# miniPET_final.net
KiCad netlist of a schematic drawn in EAGLE
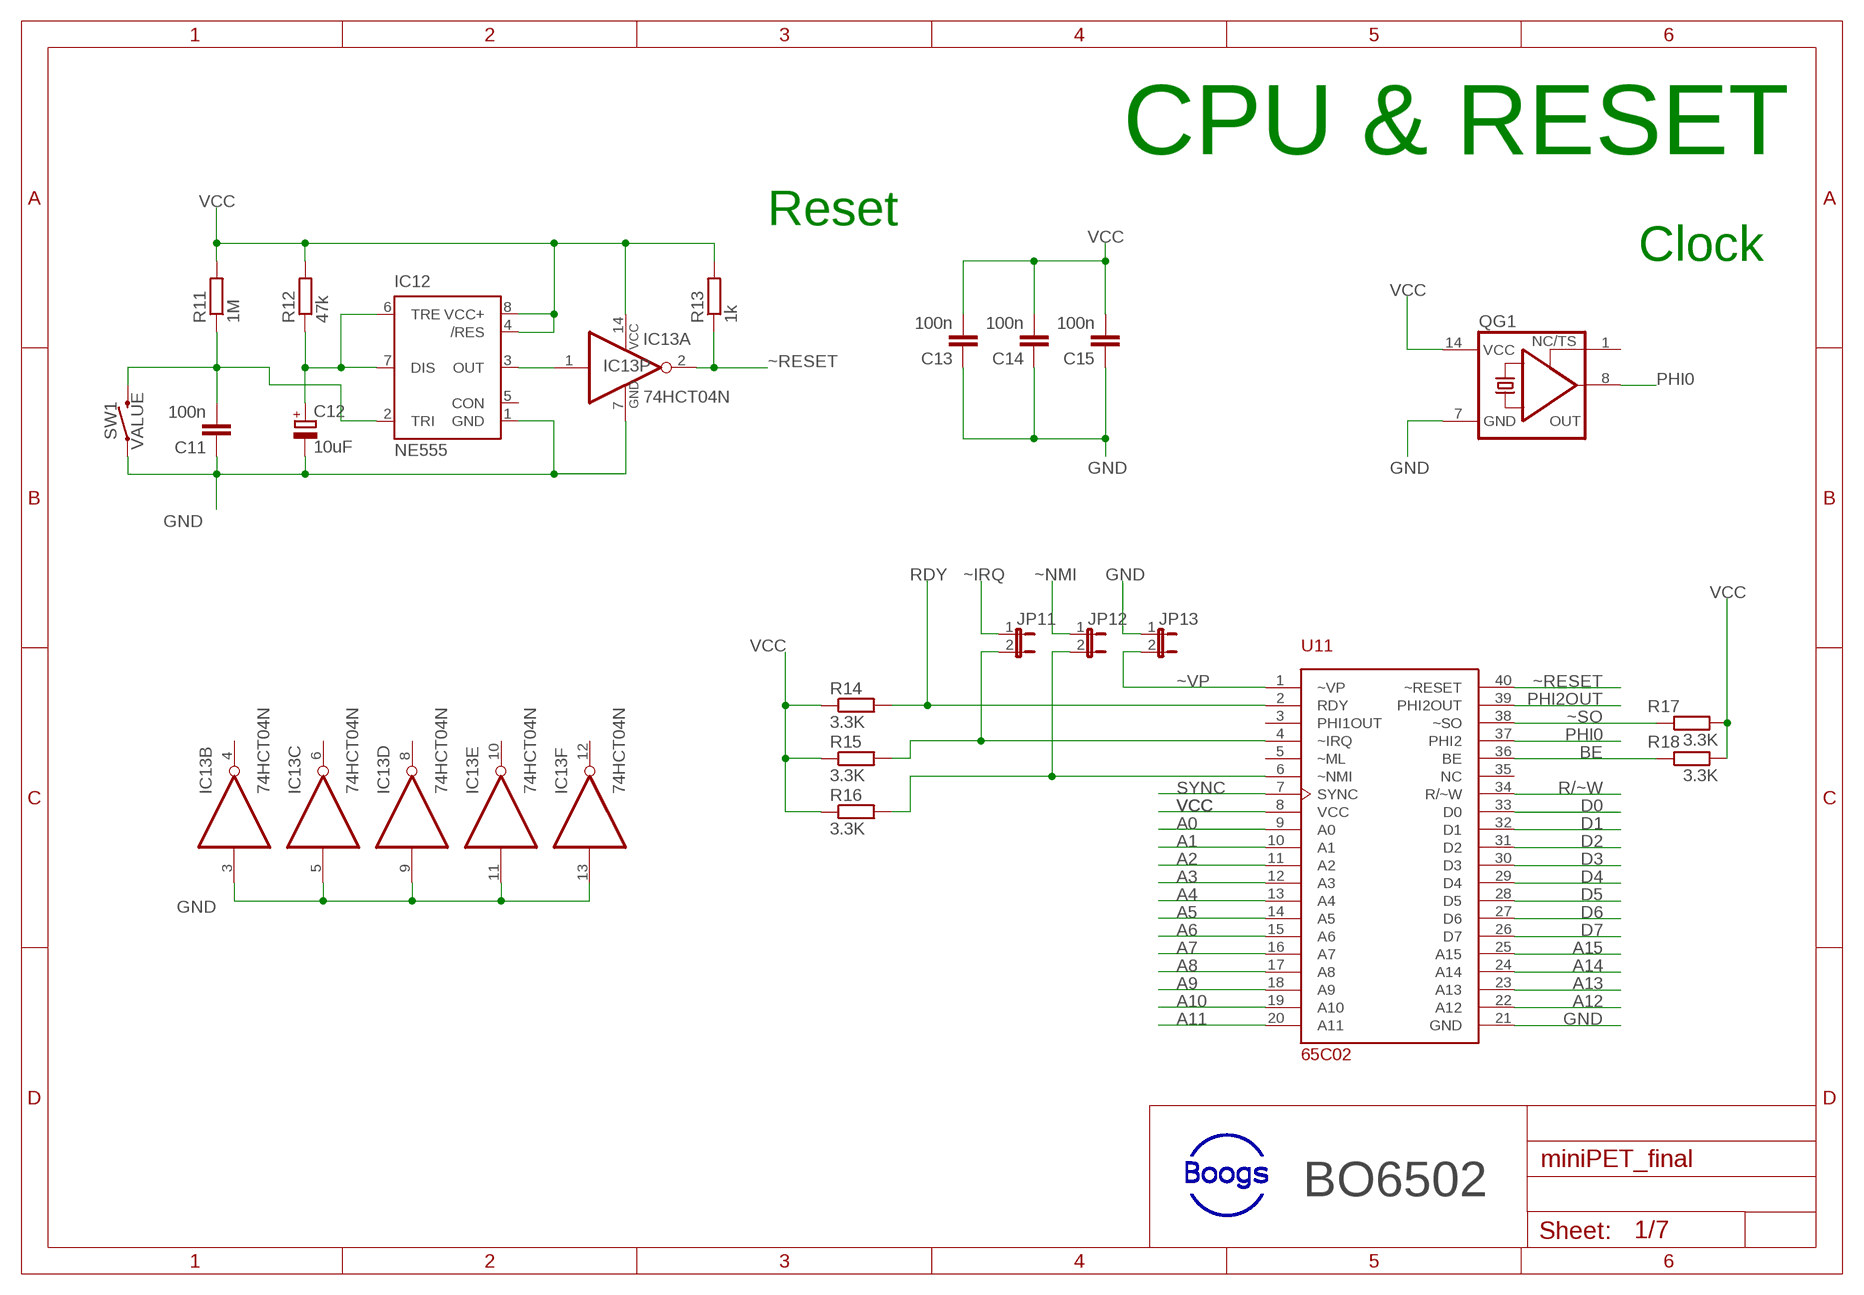
[diagram p0: schematic, sheet 1]
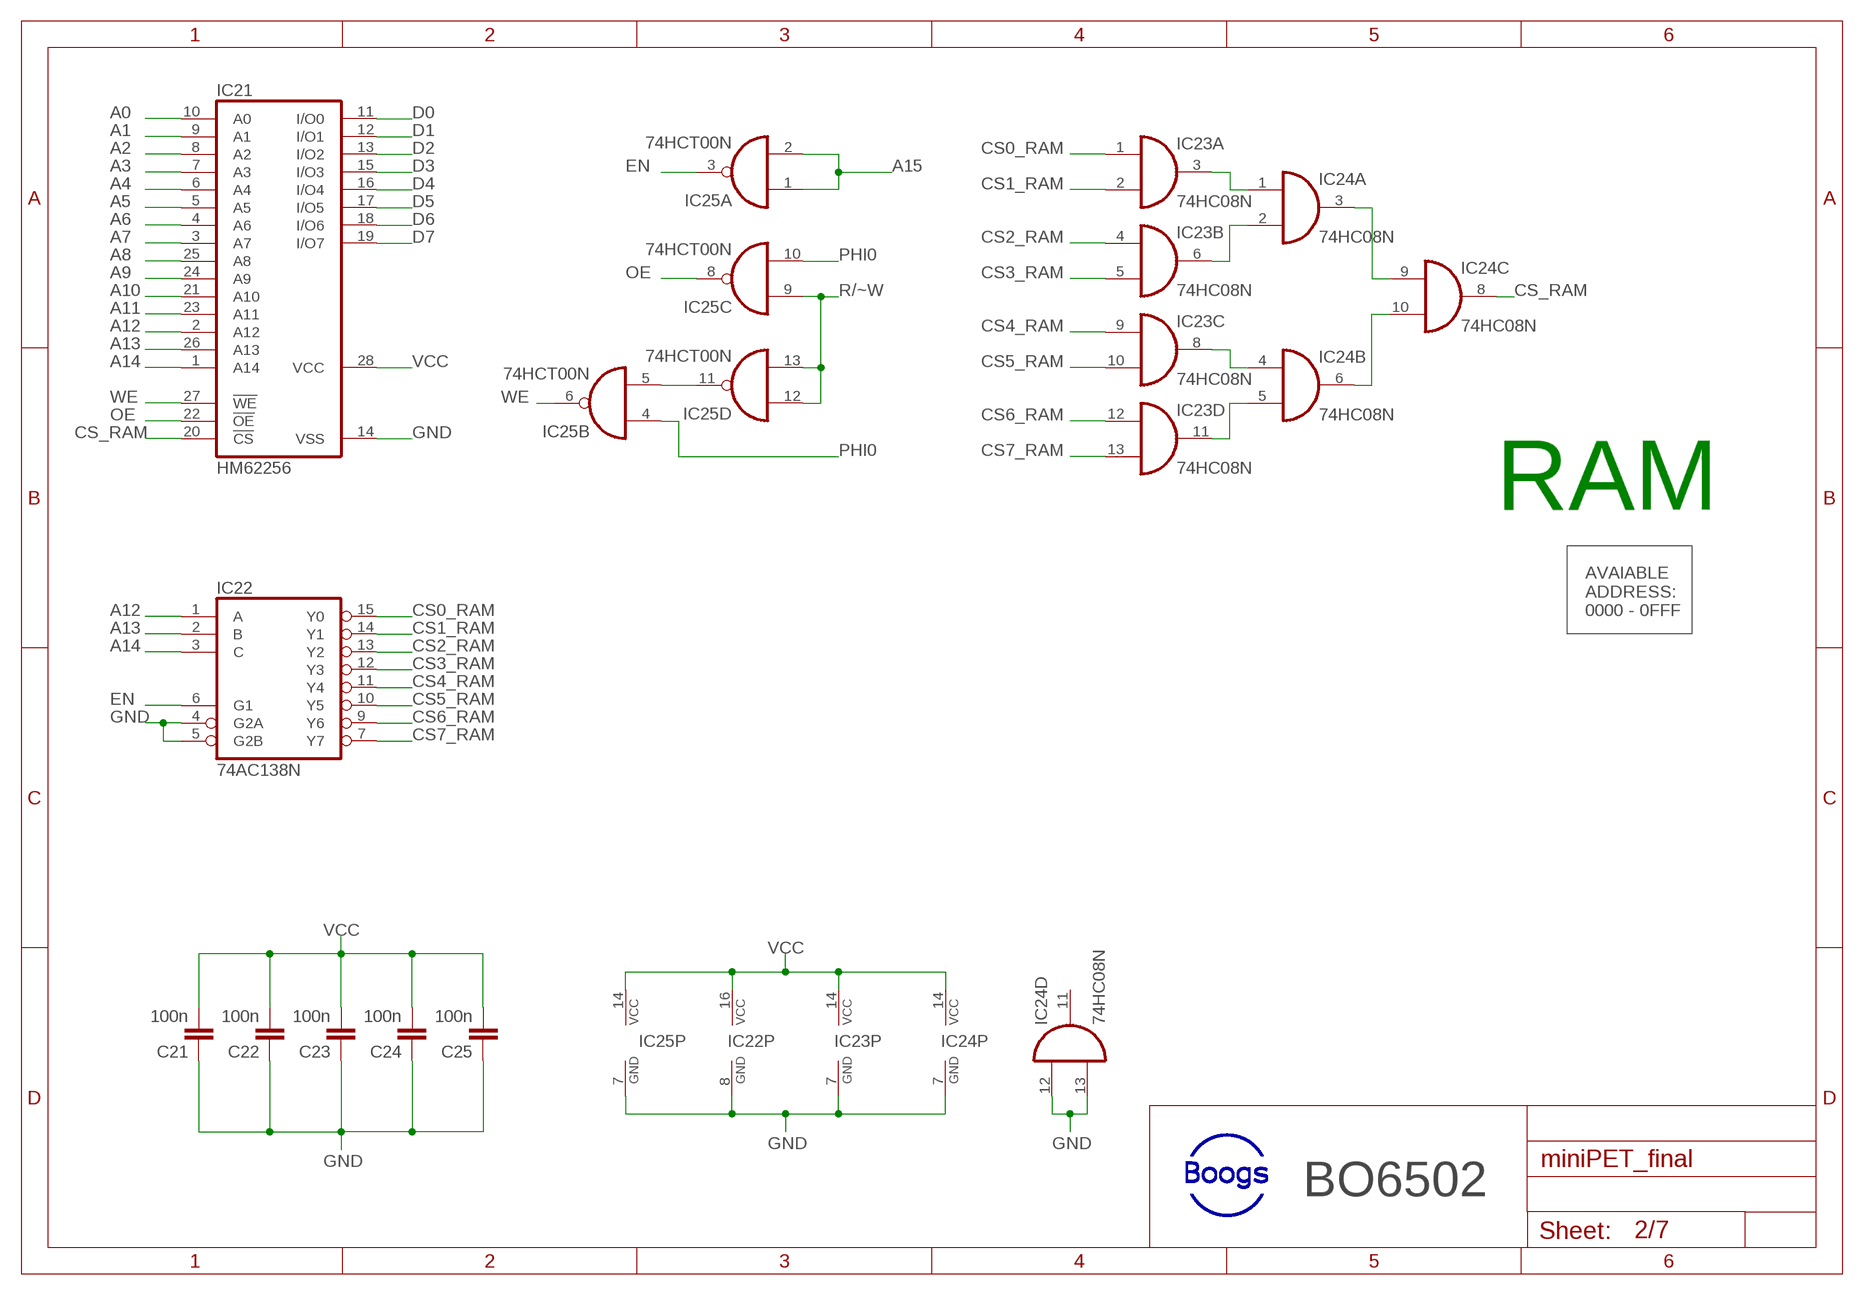
[diagram p1: schematic, sheet 2]
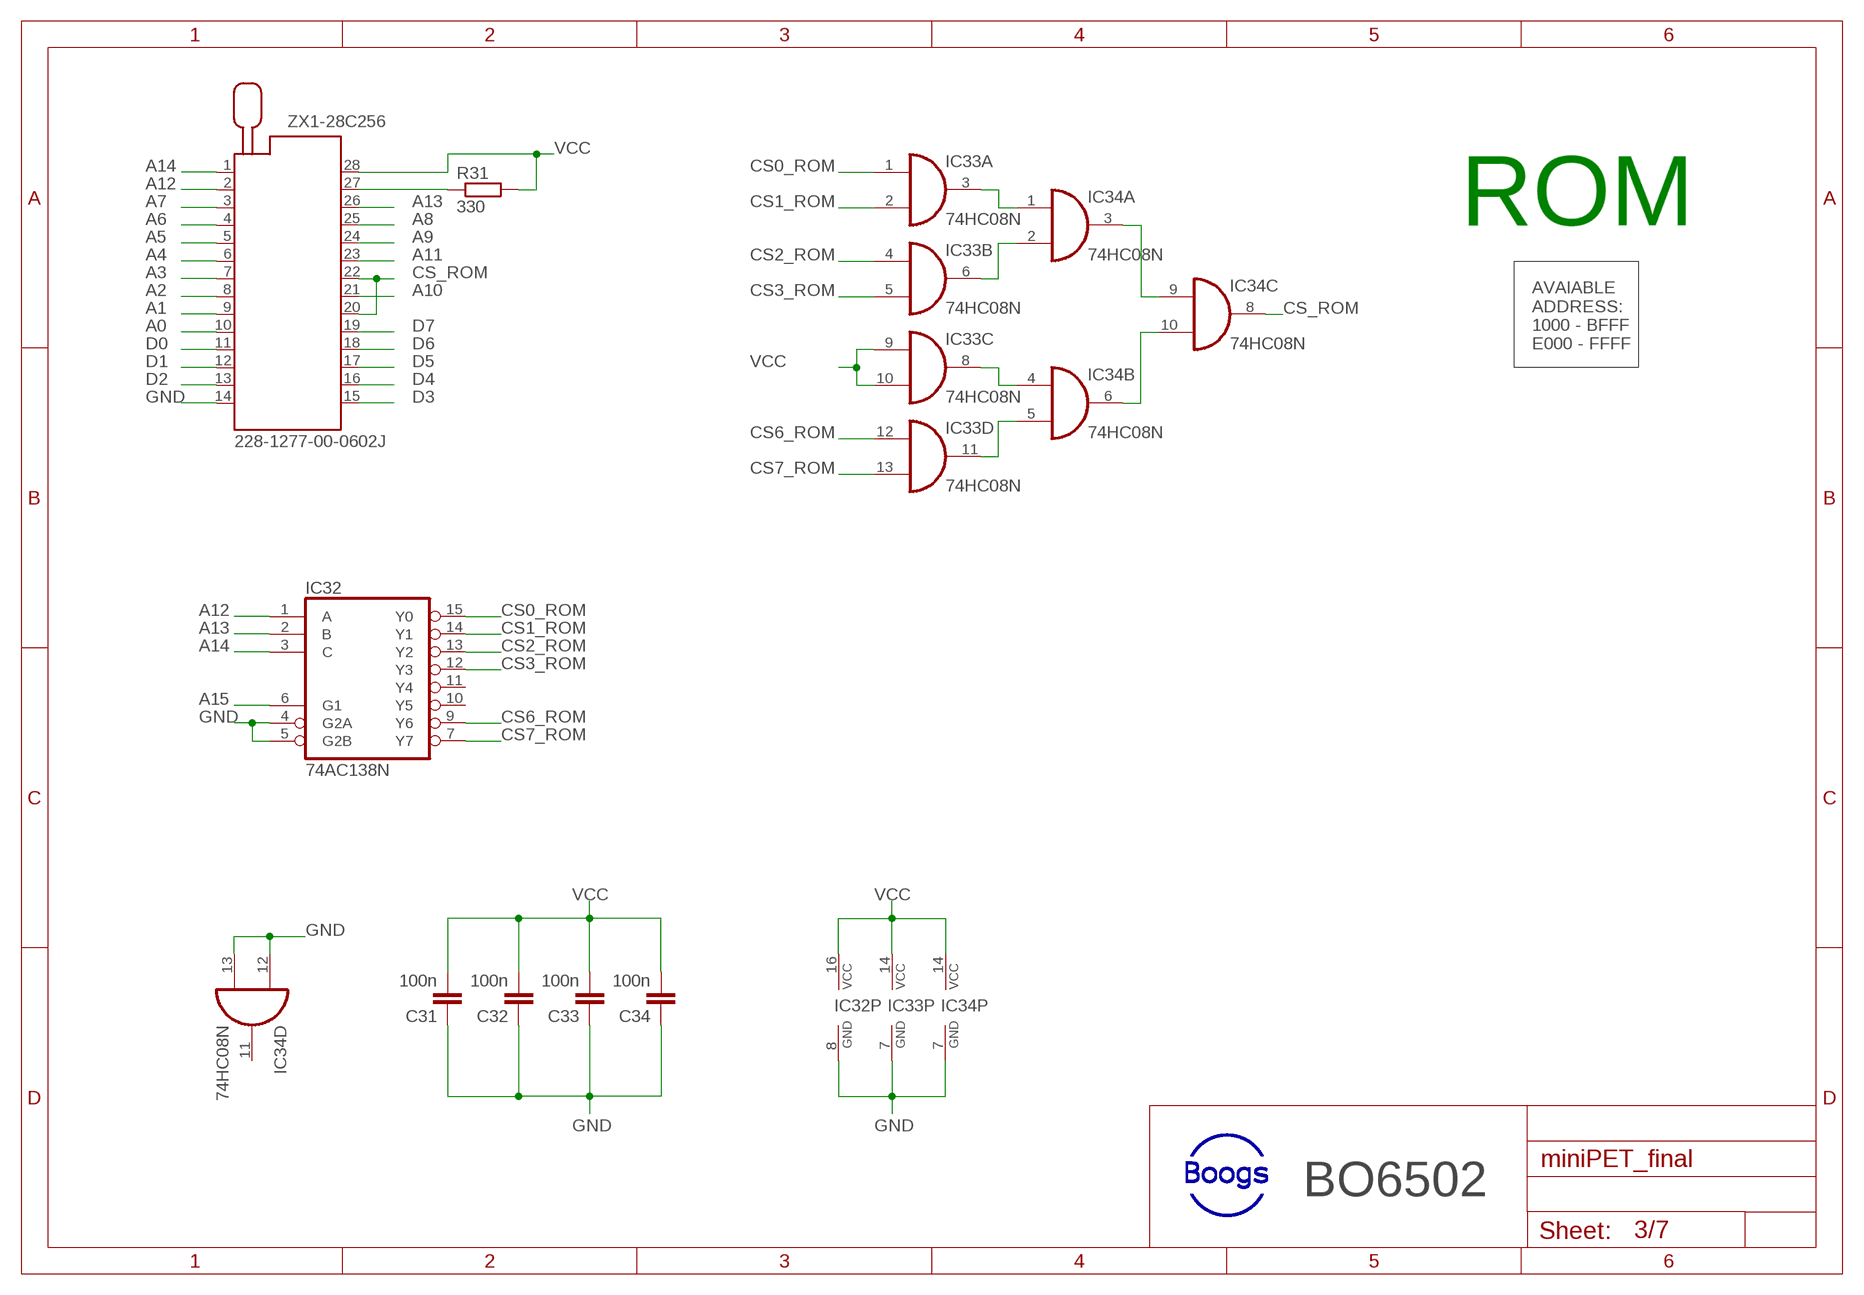
[diagram p2: schematic, sheet 3]
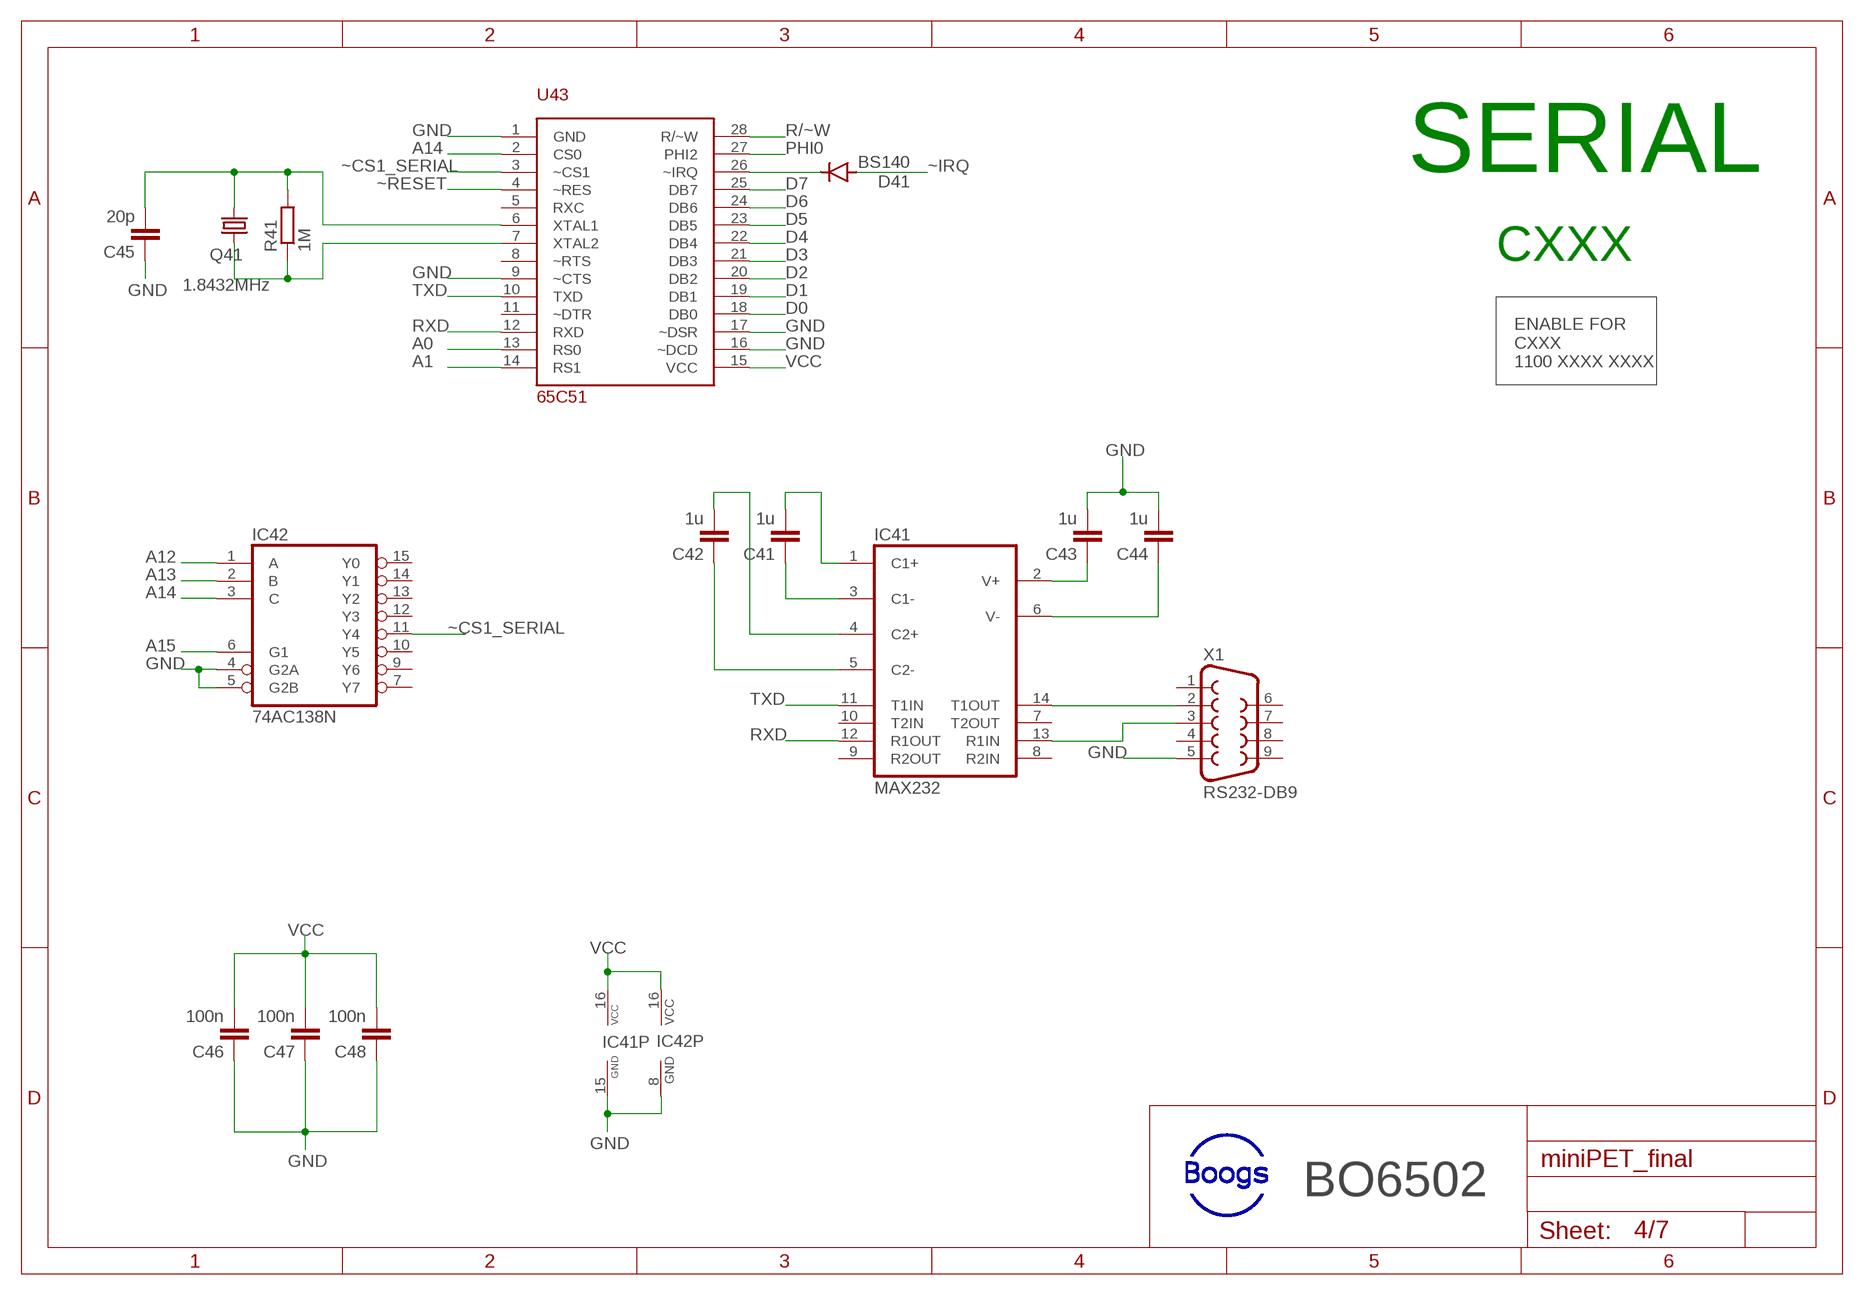
[diagram p3: schematic, sheet 4]
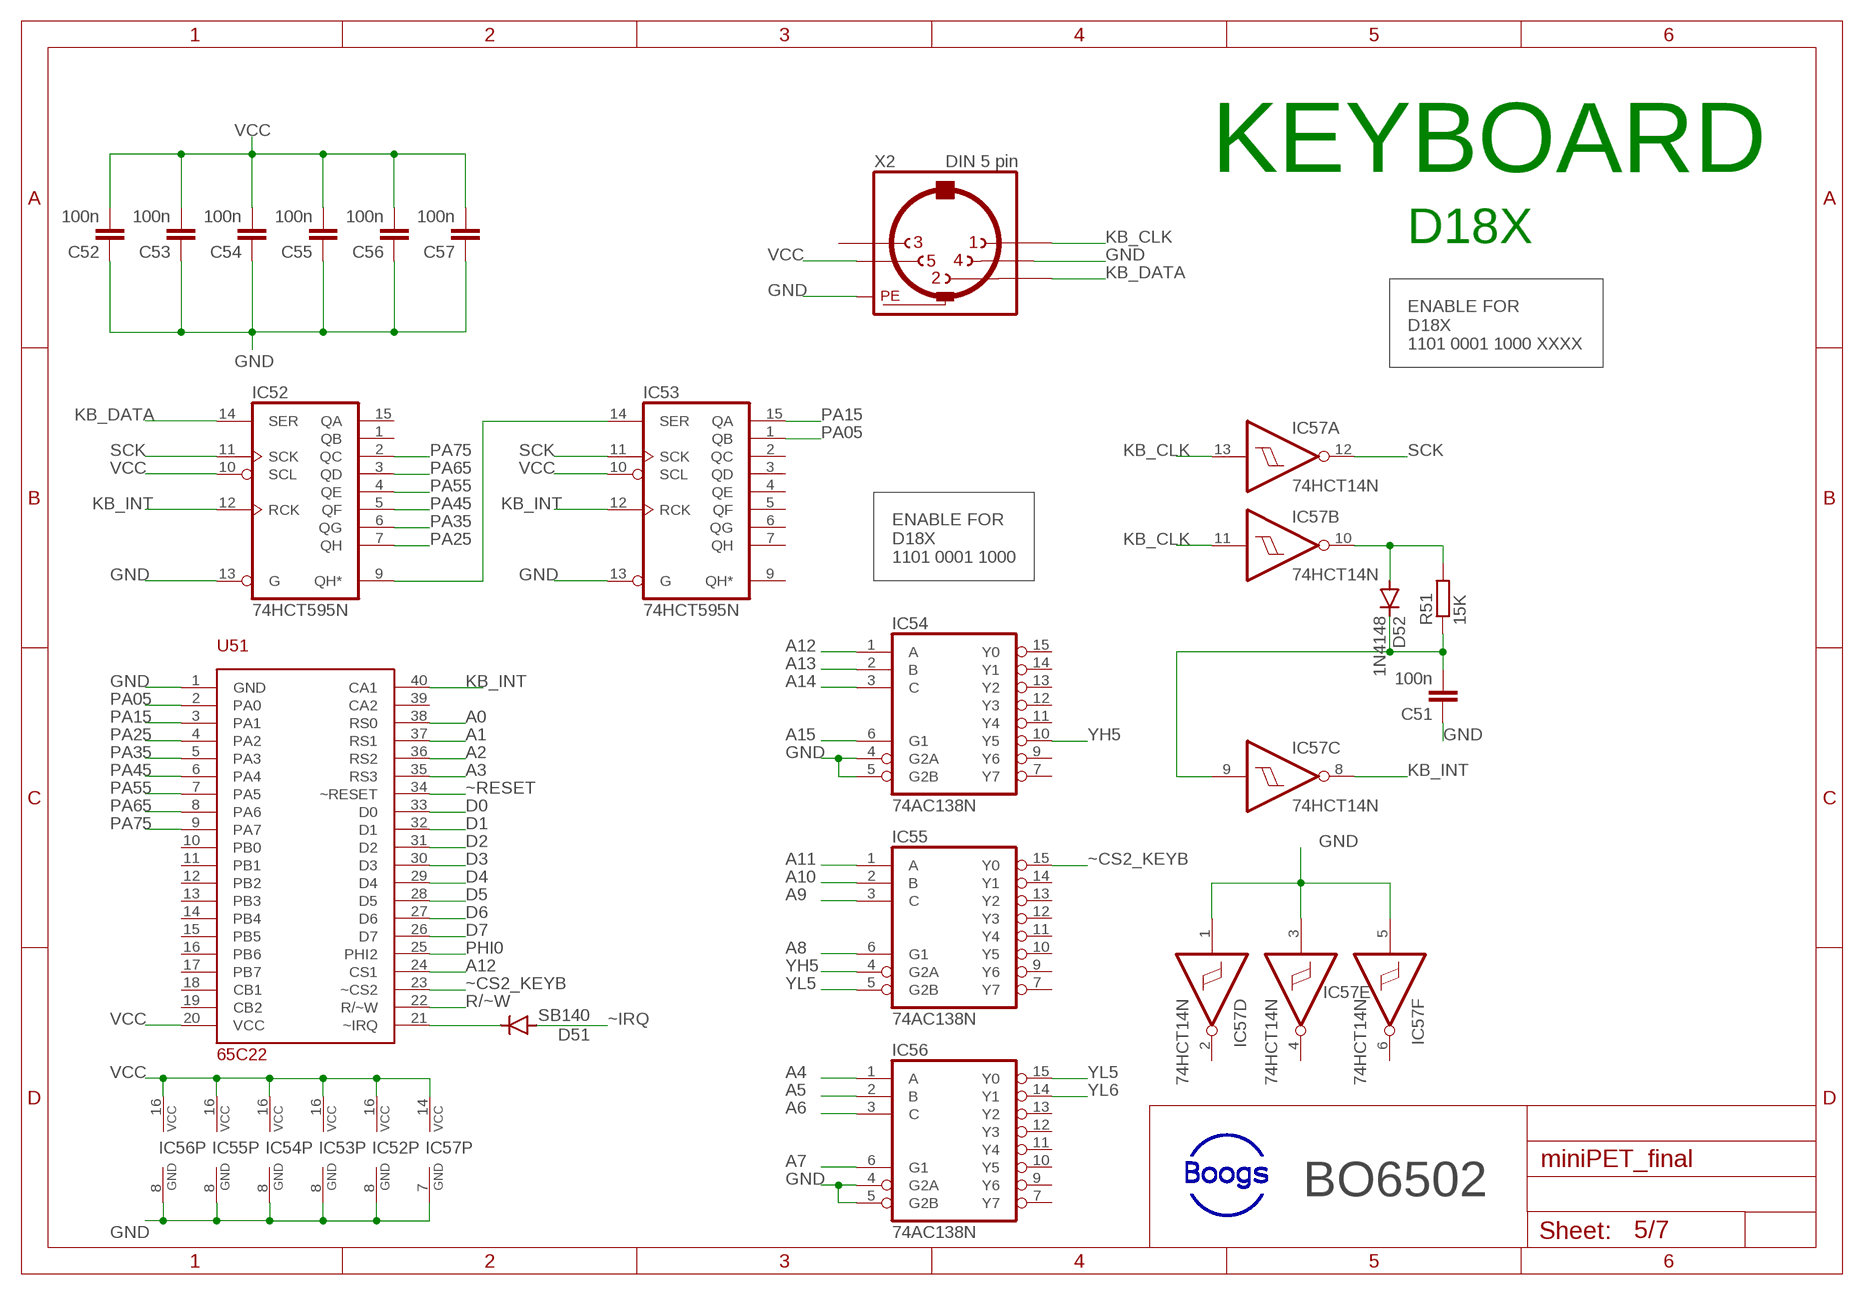
[diagram p4: schematic, sheet 5]
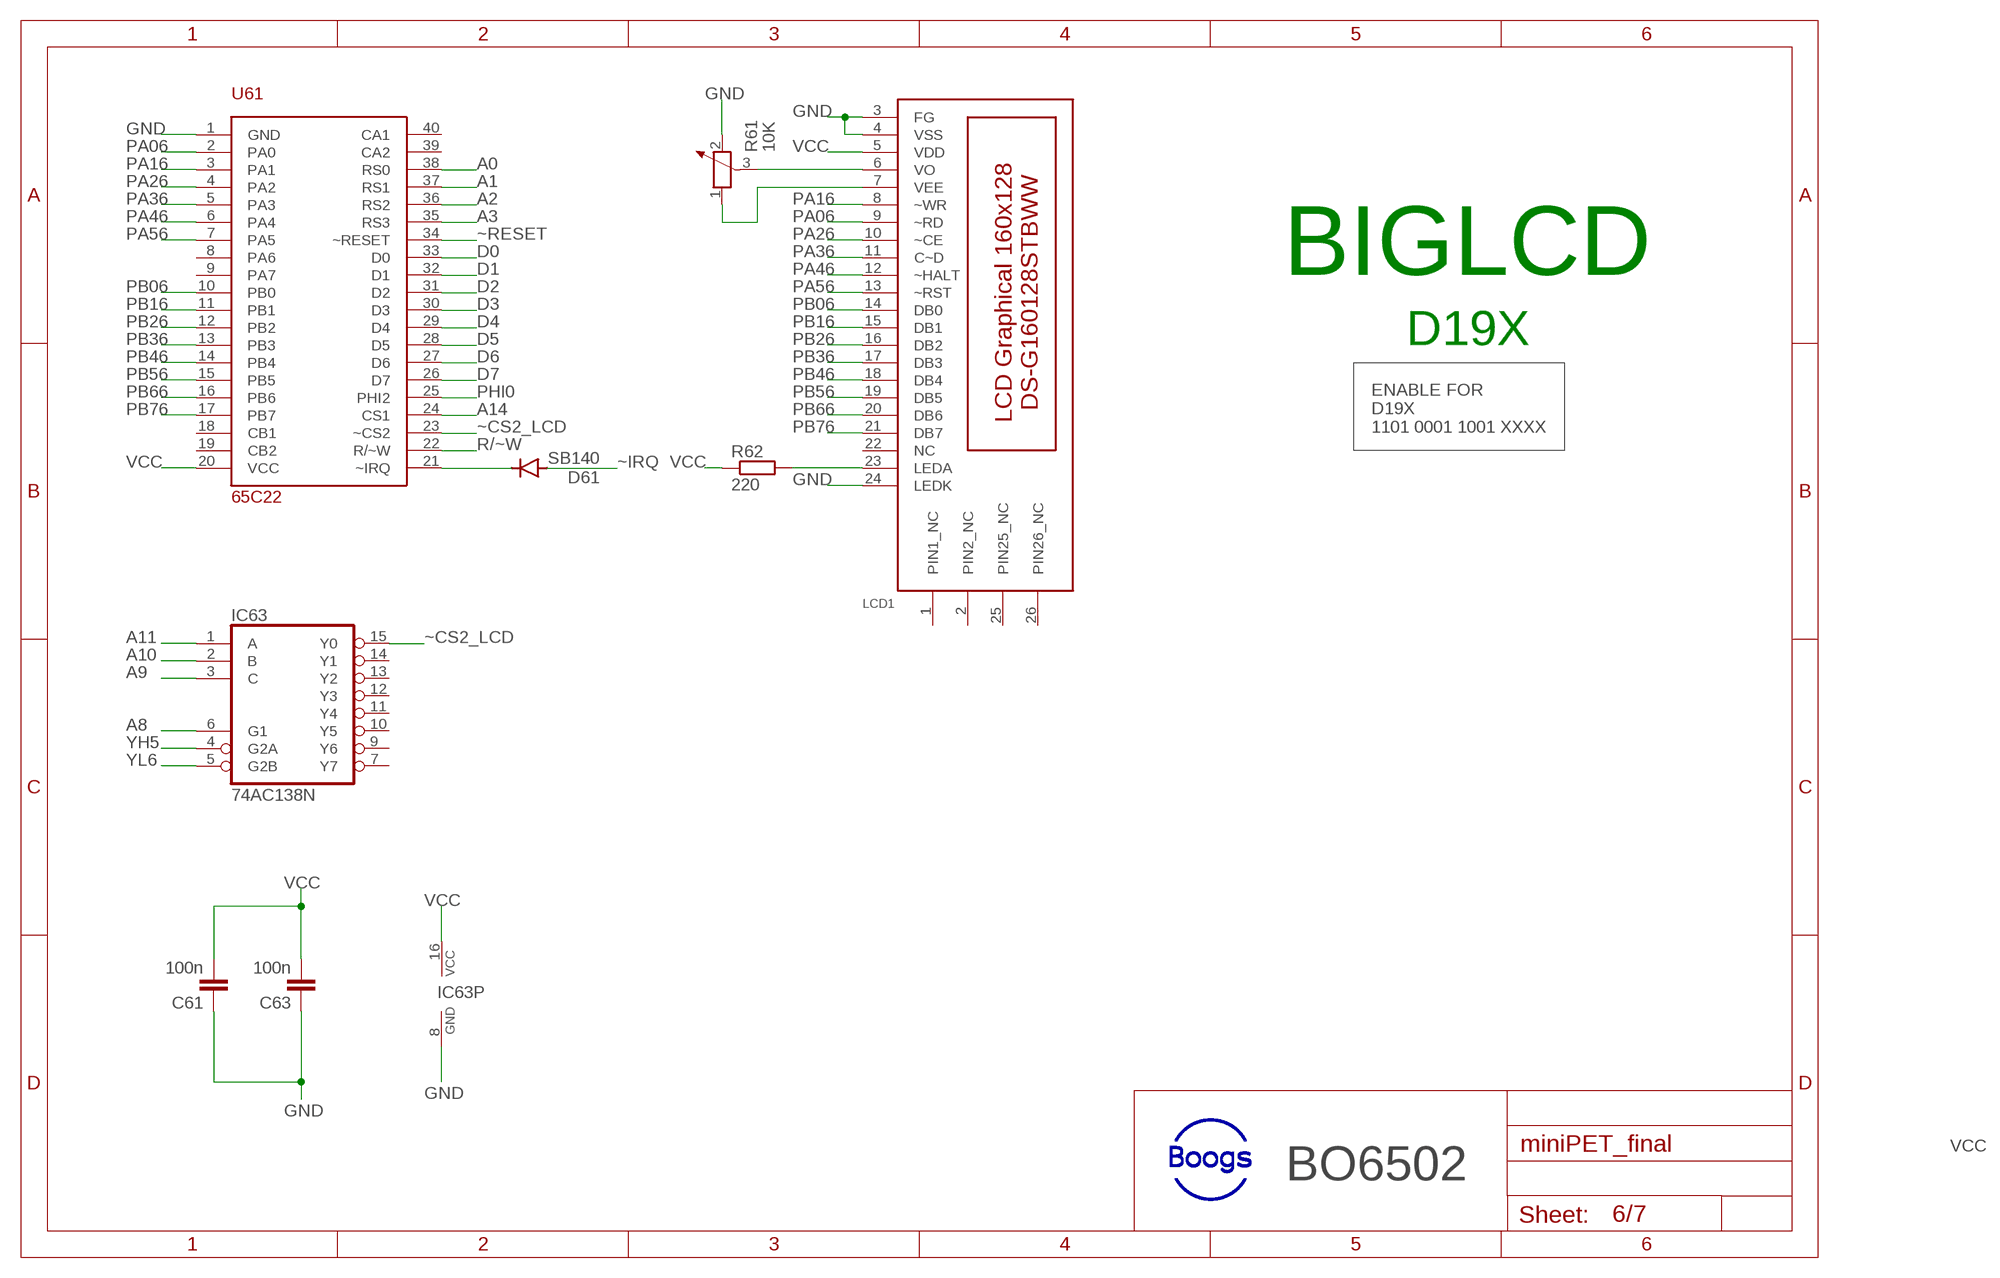
[diagram p5: schematic, sheet 6]
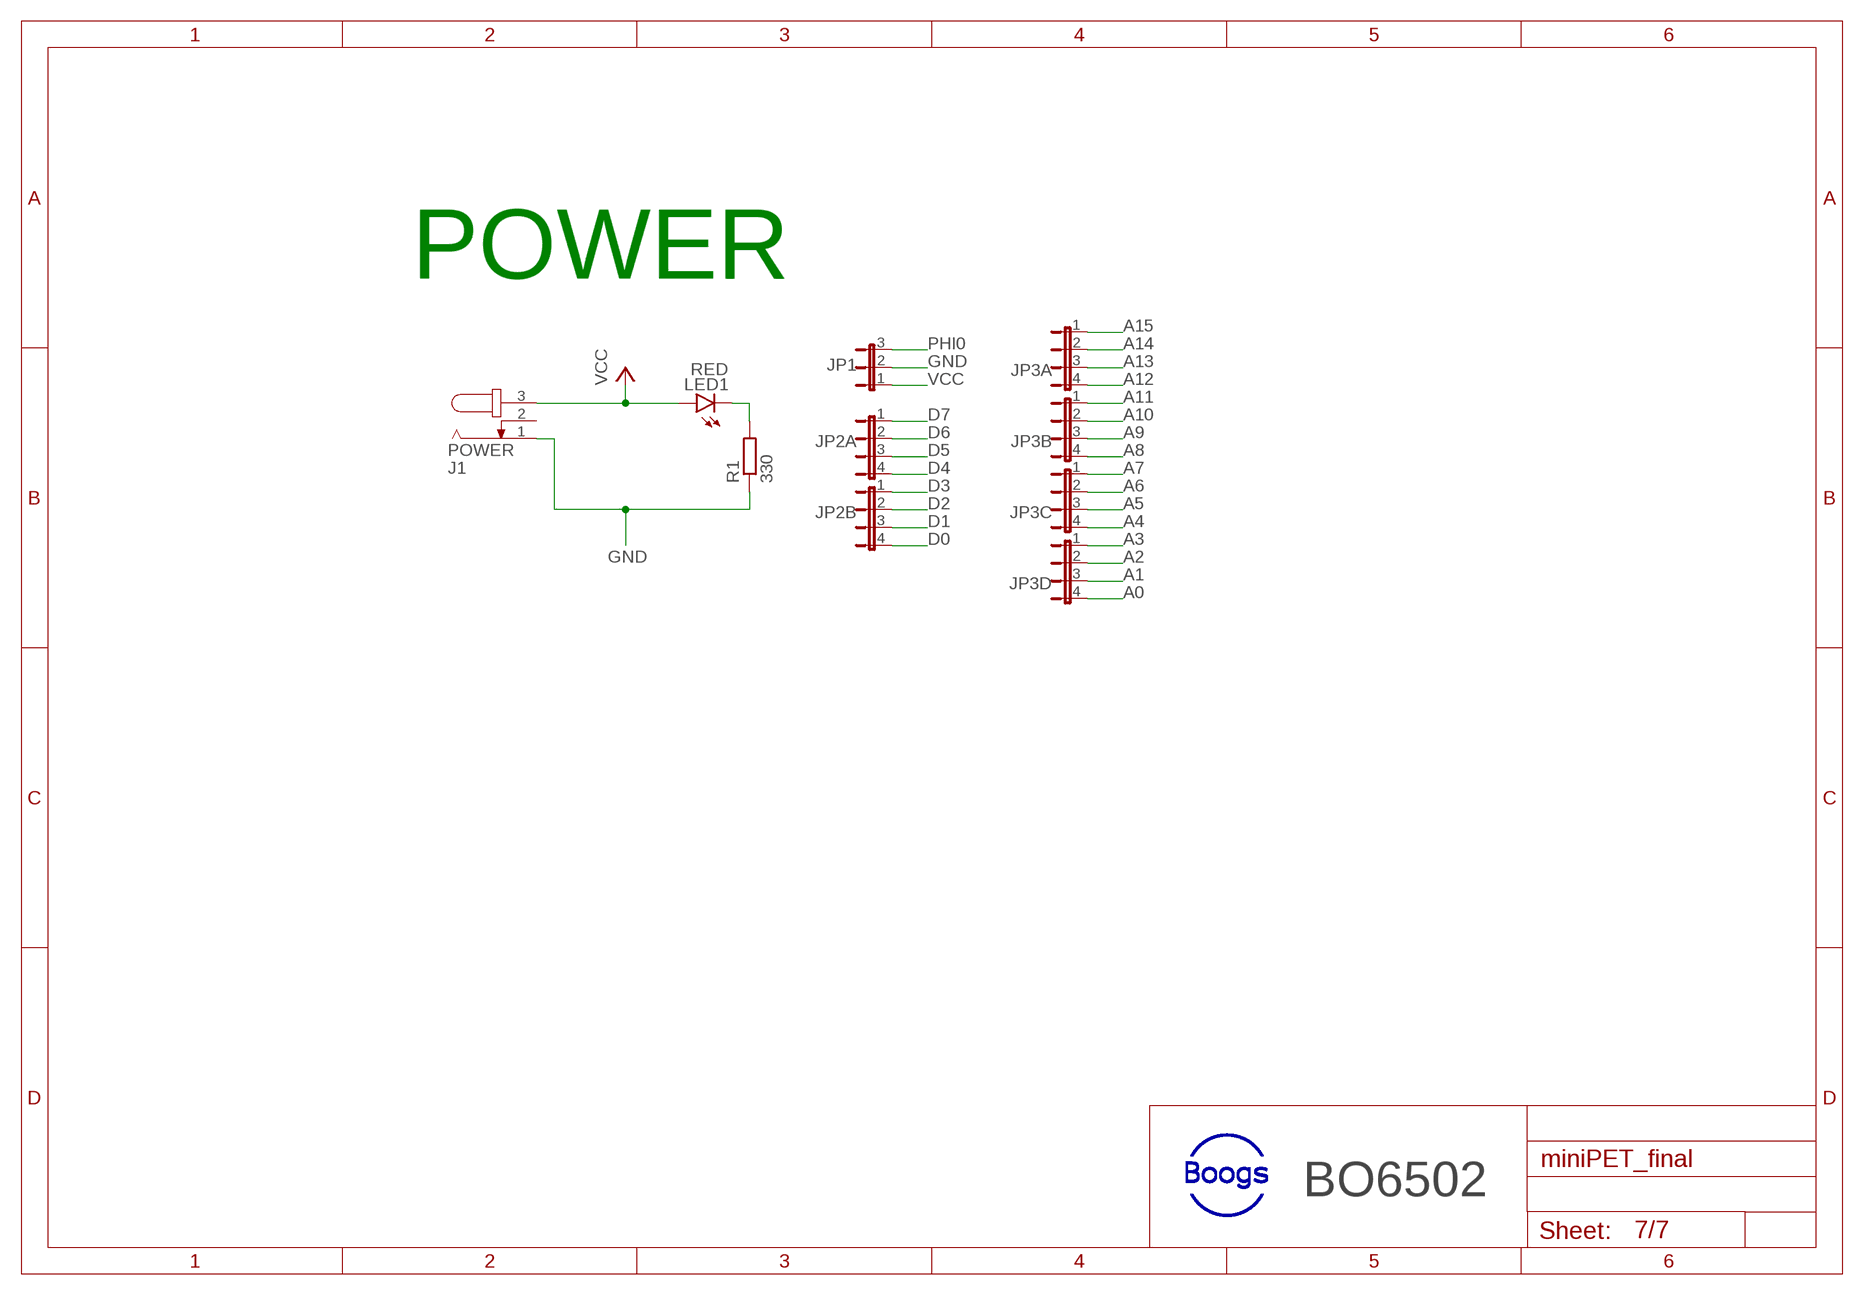
[diagram p6: schematic, sheet 7]

(export (version "E")
  (design (tool "Eeschema 10.0.6"))
  (components
    (comp (ref "C21")
      (value "100n")
      (footprint "eagle-import:C025-025X050")
      (libsource (lib "eagle-import") (part "C-EU025-025X050"))
    )
    (comp (ref "C22")
      (value "100n")
      (footprint "eagle-import:C025-025X050")
      (libsource (lib "eagle-import") (part "C-EU025-025X050"))
    )
    (comp (ref "C23")
      (value "100n")
      (footprint "eagle-import:C025-025X050")
      (libsource (lib "eagle-import") (part "C-EU025-025X050"))
    )
    (comp (ref "C24")
      (value "100n")
      (footprint "eagle-import:C025-025X050")
      (libsource (lib "eagle-import") (part "C-EU025-025X050"))
    )
    (comp (ref "C25")
      (value "100n")
      (footprint "eagle-import:C025-025X050")
      (libsource (lib "eagle-import") (part "C-EU025-025X050"))
    )
    (comp (ref "IC21")
      (value "HM62256")
      (footprint "eagle-import:DIL28-6")
      (libsource (lib "eagle-import") (part "62256P"))
    )
    (comp (ref "IC22")
      (value "74AC138N")
      (footprint "eagle-import:DIL16")
      (libsource (lib "eagle-import") (part "74138NAC"))
    )
    (comp (ref "IC23")
      (value "74HC08N")
      (footprint "eagle-import:DIL14")
      (libsource (lib "eagle-import") (part "7408NHC"))
    )
    (comp (ref "IC24")
      (value "74HC08N")
      (footprint "eagle-import:DIL14")
      (libsource (lib "eagle-import") (part "7408NHC"))
    )
    (comp (ref "IC25")
      (value "74HCT00N")
      (footprint "eagle-import:DIL14")
      (libsource (lib "eagle-import") (part "7400NHCT"))
    )
    (comp (ref "C51")
      (value "100n")
      (footprint "eagle-import:C025-025X050")
      (libsource (lib "eagle-import") (part "C-EU025-025X050"))
    )
    (comp (ref "C52")
      (value "100n")
      (footprint "eagle-import:C025-025X050")
      (libsource (lib "eagle-import") (part "C-EU025-025X050"))
    )
    (comp (ref "C53")
      (value "100n")
      (footprint "eagle-import:C025-025X050")
      (libsource (lib "eagle-import") (part "C-EU025-025X050"))
    )
    (comp (ref "C54")
      (value "100n")
      (footprint "eagle-import:C025-025X050")
      (libsource (lib "eagle-import") (part "C-EU025-025X050"))
    )
    (comp (ref "C55")
      (value "100n")
      (footprint "eagle-import:C025-025X050")
      (libsource (lib "eagle-import") (part "C-EU025-025X050"))
    )
    (comp (ref "C56")
      (value "100n")
      (footprint "eagle-import:C025-025X050")
      (libsource (lib "eagle-import") (part "C-EU025-025X050"))
    )
    (comp (ref "C57")
      (value "100n")
      (footprint "eagle-import:C025-025X050")
      (libsource (lib "eagle-import") (part "C-EU025-025X050"))
    )
    (comp (ref "D51")
      (value "SB140")
      (footprint "eagle-import:DO41-10")
      (libsource (lib "eagle-import") (part "1N4004"))
    )
    (comp (ref "D52")
      (value "1N4148")
      (footprint "eagle-import:DO35-7")
      (libsource (lib "eagle-import") (part "1N4148DO35-7"))
    )
    (comp (ref "IC52")
      (value "74HCT595N")
      (footprint "eagle-import:DIL16")
      (libsource (lib "eagle-import") (part "74595NHCT"))
    )
    (comp (ref "IC53")
      (value "74HCT595N")
      (footprint "eagle-import:DIL16")
      (libsource (lib "eagle-import") (part "74595NHCT"))
    )
    (comp (ref "IC54")
      (value "74AC138N")
      (footprint "eagle-import:DIL16")
      (libsource (lib "eagle-import") (part "74138NAC"))
    )
    (comp (ref "IC55")
      (value "74AC138N")
      (footprint "eagle-import:DIL16")
      (libsource (lib "eagle-import") (part "74138NAC"))
    )
    (comp (ref "IC56")
      (value "74AC138N")
      (footprint "eagle-import:DIL16")
      (libsource (lib "eagle-import") (part "74138NAC"))
    )
    (comp (ref "IC57")
      (value "74HCT14N")
      (footprint "eagle-import:DIL14")
      (libsource (lib "eagle-import") (part "7414NHCT"))
    )
    (comp (ref "R51")
      (value "15K")
      (footprint "eagle-import:0207_10")
      (libsource (lib "eagle-import") (part "R-EU_0207/10"))
    )
    (comp (ref "U51")
      (value "65C22")
      (footprint "eagle-import:DIL40")
      (libsource (lib "eagle-import") (part "65C22"))
    )
    (comp (ref "X2")
      (value "DIN 5 pin")
      (footprint "eagle-import:MAB5SH")
      (libsource (lib "eagle-import") (part "MAB5SH"))
    )
    (comp (ref "C61")
      (value "100n")
      (footprint "eagle-import:C025-025X050")
      (libsource (lib "eagle-import") (part "C-EU025-025X050"))
    )
    (comp (ref "C63")
      (value "100n")
      (footprint "eagle-import:C025-025X050")
      (libsource (lib "eagle-import") (part "C-EU025-025X050"))
    )
    (comp (ref "D61")
      (value "SB140")
      (footprint "eagle-import:DO41-10")
      (libsource (lib "eagle-import") (part "1N4004"))
    )
    (comp (ref "IC63")
      (value "74AC138N")
      (footprint "eagle-import:DIL16")
      (libsource (lib "eagle-import") (part "74138NAC"))
    )
    (comp (ref "LCD1")
      (value "DS-G160128STBWW")
      (footprint "eagle-import:PAK100_2500-26")
      (libsource (lib "eagle-import") (part "DS-G160128STBWW"))
    )
    (comp (ref "R61")
      (value "10K")
      (footprint "eagle-import:PT-10")
      (libsource (lib "eagle-import") (part "POTENTIOMETER_PT-10"))
    )
    (comp (ref "R62")
      (value "220")
      (footprint "eagle-import:0207_10")
      (libsource (lib "eagle-import") (part "R-EU_0207/10"))
    )
    (comp (ref "U61")
      (value "65C22")
      (footprint "eagle-import:DIL40")
      (libsource (lib "eagle-import") (part "65C22"))
    )
    (comp (ref "C11")
      (value "100n")
      (footprint "eagle-import:C025-025X050")
      (libsource (lib "eagle-import") (part "C-EU025-025X050"))
    )
    (comp (ref "C12")
      (value "10uF")
      (footprint "eagle-import:B45181A")
      (libsource (lib "eagle-import") (part "CPOL-EUB45181A"))
    )
    (comp (ref "C13")
      (value "100n")
      (footprint "eagle-import:C025-025X050")
      (libsource (lib "eagle-import") (part "C-EU025-025X050"))
    )
    (comp (ref "C14")
      (value "100n")
      (footprint "eagle-import:C025-025X050")
      (libsource (lib "eagle-import") (part "C-EU025-025X050"))
    )
    (comp (ref "C15")
      (value "100n")
      (footprint "eagle-import:C025-025X050")
      (libsource (lib "eagle-import") (part "C-EU025-025X050"))
    )
    (comp (ref "IC12")
      (value "NE555")
      (footprint "eagle-import:DIL-08")
      (fields (field (name "MF") "Arrow Electronics") (field (name "MPN") "NE555N"))
      (libsource (lib "eagle-import") (part "NE555"))
    )
    (comp (ref "IC13")
      (value "74HCT04N")
      (footprint "eagle-import:DIL14")
      (libsource (lib "eagle-import") (part "7404NHCT"))
    )
    (comp (ref "JP11")
      (value "JP1E")
      (footprint "eagle-import:JP1")
      (libsource (lib "eagle-import") (part "JP1E"))
    )
    (comp (ref "JP12")
      (value "JP1E")
      (footprint "eagle-import:JP1")
      (libsource (lib "eagle-import") (part "JP1E"))
    )
    (comp (ref "JP13")
      (value "JP1E")
      (footprint "eagle-import:JP1")
      (libsource (lib "eagle-import") (part "JP1E"))
    )
    (comp (ref "QG1")
      (value "XO-14")
      (footprint "eagle-import:DIL14S")
      (libsource (lib "eagle-import") (part "XO-14"))
    )
    (comp (ref "R11")
      (value "1M")
      (footprint "eagle-import:0207_10")
      (libsource (lib "eagle-import") (part "R-EU_0207/10"))
    )
    (comp (ref "R12")
      (value "47k")
      (footprint "eagle-import:0207_10")
      (libsource (lib "eagle-import") (part "R-EU_0207/10"))
    )
    (comp (ref "R13")
      (value "1k")
      (footprint "eagle-import:0207_10")
      (libsource (lib "eagle-import") (part "R-EU_0207/10"))
    )
    (comp (ref "R14")
      (value "3.3K")
      (footprint "eagle-import:0207_10")
      (libsource (lib "eagle-import") (part "R-EU_0207/10"))
    )
    (comp (ref "R15")
      (value "3.3K")
      (footprint "eagle-import:0207_10")
      (libsource (lib "eagle-import") (part "R-EU_0207/10"))
    )
    (comp (ref "R16")
      (value "3.3K")
      (footprint "eagle-import:0207_10")
      (libsource (lib "eagle-import") (part "R-EU_0207/10"))
    )
    (comp (ref "R17")
      (value "3.3K")
      (footprint "eagle-import:0207_10")
      (libsource (lib "eagle-import") (part "R-EU_0207/10"))
    )
    (comp (ref "R18")
      (value "3.3K")
      (footprint "eagle-import:0207_10")
      (libsource (lib "eagle-import") (part "R-EU_0207/10"))
    )
    (comp (ref "SW1")
      (value "MOMENTARY-SWITCH-SPST-PTH-RIGHT-ANGLE-8-020")
      (footprint "eagle-import:TACTILE_SWITCH_PTH_RA_8-020")
      (libsource (lib "eagle-import") (part "MOMENTARY-SWITCH-SPST-PTH-RIGHT-ANGLE-8-020"))
    )
    (comp (ref "U11")
      (value "65C02")
      (footprint "eagle-import:DIL40")
      (libsource (lib "eagle-import") (part "65C02"))
    )
    (comp (ref "C31")
      (value "100n")
      (footprint "eagle-import:C025-025X050")
      (libsource (lib "eagle-import") (part "C-EU025-025X050"))
    )
    (comp (ref "C32")
      (value "100n")
      (footprint "eagle-import:C025-025X050")
      (libsource (lib "eagle-import") (part "C-EU025-025X050"))
    )
    (comp (ref "C33")
      (value "100n")
      (footprint "eagle-import:C025-025X050")
      (libsource (lib "eagle-import") (part "C-EU025-025X050"))
    )
    (comp (ref "C34")
      (value "100n")
      (footprint "eagle-import:C025-025X050")
      (libsource (lib "eagle-import") (part "C-EU025-025X050"))
    )
    (comp (ref "IC32")
      (value "74AC138N")
      (footprint "eagle-import:DIL16")
      (libsource (lib "eagle-import") (part "74138NAC"))
    )
    (comp (ref "IC33")
      (value "74HC08N")
      (footprint "eagle-import:DIL14")
      (libsource (lib "eagle-import") (part "7408NHC"))
    )
    (comp (ref "IC34")
      (value "74HC08N")
      (footprint "eagle-import:DIL14")
      (libsource (lib "eagle-import") (part "7408NHC"))
    )
    (comp (ref "R31")
      (value "330")
      (footprint "eagle-import:0207_10")
      (libsource (lib "eagle-import") (part "R-EU_0207/10"))
    )
    (comp (ref "ZX1-28C256")
      (value "228-1277-00-0602J")
      (footprint "eagle-import:228-1277-00-0602J")
      (fields (field (name "MF") "3M"))
      (libsource (lib "eagle-import") (part "228-?00-0602J1277-"))
    )
    (comp (ref "C41")
      (value "1u")
      (footprint "eagle-import:C050-025X075")
      (libsource (lib "eagle-import") (part "C-EU050-025X075"))
    )
    (comp (ref "C42")
      (value "1u")
      (footprint "eagle-import:C050-025X075")
      (libsource (lib "eagle-import") (part "C-EU050-025X075"))
    )
    (comp (ref "C43")
      (value "1u")
      (footprint "eagle-import:C050-025X075")
      (libsource (lib "eagle-import") (part "C-EU050-025X075"))
    )
    (comp (ref "C44")
      (value "1u")
      (footprint "eagle-import:C050-025X075")
      (libsource (lib "eagle-import") (part "C-EU050-025X075"))
    )
    (comp (ref "C45")
      (value "20p")
      (footprint "eagle-import:C025-025X050")
      (libsource (lib "eagle-import") (part "C-EU025-025X050"))
    )
    (comp (ref "C46")
      (value "100n")
      (footprint "eagle-import:C025-025X050")
      (libsource (lib "eagle-import") (part "C-EU025-025X050"))
    )
    (comp (ref "C47")
      (value "100n")
      (footprint "eagle-import:C025-025X050")
      (libsource (lib "eagle-import") (part "C-EU025-025X050"))
    )
    (comp (ref "C48")
      (value "100n")
      (footprint "eagle-import:C025-025X050")
      (libsource (lib "eagle-import") (part "C-EU025-025X050"))
    )
    (comp (ref "D41")
      (value "BS140")
      (footprint "eagle-import:DO41-10")
      (libsource (lib "eagle-import") (part "1N4004"))
    )
    (comp (ref "IC41")
      (value "MAX232")
      (footprint "eagle-import:DIL16")
      (fields (field (name "MF") "MAXIM") (field (name "MPN") "MAX232ACPE+"))
      (libsource (lib "eagle-import") (part "MAX232"))
    )
    (comp (ref "IC42")
      (value "74AC138N")
      (footprint "eagle-import:DIL16")
      (libsource (lib "eagle-import") (part "74138NAC"))
    )
    (comp (ref "Q41")
      (value "1.8432MHz")
      (footprint "eagle-import:HC49_S")
      (libsource (lib "eagle-import") (part "CRYSTALHC49S"))
    )
    (comp (ref "R41")
      (value "1M")
      (footprint "eagle-import:0207_10")
      (libsource (lib "eagle-import") (part "R-EU_0207/10"))
    )
    (comp (ref "U43")
      (value "65C51")
      (footprint "eagle-import:DIL28")
      (libsource (lib "eagle-import") (part "65C51"))
    )
    (comp (ref "X1")
      (value "RS232-DB9")
      (footprint "eagle-import:F09HP")
      (libsource (lib "eagle-import") (part "F09HP"))
    )
    (comp (ref "J1")
      (value "POWER")
      (footprint "eagle-import:SPC4078")
      (libsource (lib "eagle-import") (part "JACK-PLUG1"))
    )
    (comp (ref "JP1")
      (value "JP2E")
      (footprint "eagle-import:JP2")
      (libsource (lib "eagle-import") (part "JP2E"))
    )
    (comp (ref "JP2A")
      (value "JP4E")
      (footprint "eagle-import:JP4")
      (libsource (lib "eagle-import") (part "JP4E"))
    )
    (comp (ref "JP2B")
      (value "JP4E")
      (footprint "eagle-import:JP4")
      (libsource (lib "eagle-import") (part "JP4E"))
    )
    (comp (ref "JP3A")
      (value "JP4E")
      (footprint "eagle-import:JP4")
      (libsource (lib "eagle-import") (part "JP4E"))
    )
    (comp (ref "JP3B")
      (value "JP4E")
      (footprint "eagle-import:JP4")
      (libsource (lib "eagle-import") (part "JP4E"))
    )
    (comp (ref "JP3C")
      (value "JP4E")
      (footprint "eagle-import:JP4")
      (libsource (lib "eagle-import") (part "JP4E"))
    )
    (comp (ref "JP3D")
      (value "JP4E")
      (footprint "eagle-import:JP4")
      (libsource (lib "eagle-import") (part "JP4E"))
    )
    (comp (ref "LED1")
      (value "RED")
      (footprint "eagle-import:LED5MM")
      (libsource (lib "eagle-import") (part "LED5MM"))
    )
    (comp (ref "R1")
      (value "330")
      (footprint "eagle-import:0207_10")
      (libsource (lib "eagle-import") (part "R-EU_0207/10"))
    )
  )
  (nets
    (net (code "1") (name "A0") (class "Default")
      (node (ref "IC21") (pin "10") (pinfunction "A0_10") (pintype "input"))
      (node (ref "JP3D") (pin "4") (pinfunction "4_4") (pintype "passive"))
      (node (ref "U11") (pin "9") (pinfunction "A0_9") (pintype "bidirectional"))
      (node (ref "U43") (pin "13") (pinfunction "RS0_13") (pintype "bidirectional"))
      (node (ref "U51") (pin "38") (pinfunction "RS0_38") (pintype "bidirectional"))
      (node (ref "U61") (pin "38") (pinfunction "RS0_38") (pintype "bidirectional"))
      (node (ref "ZX1-28C256") (pin "10") (pinfunction "10_10") (pintype "passive"))
    )
    (net (code "2") (name "A1") (class "Default")
      (node (ref "IC21") (pin "9") (pinfunction "A1_9") (pintype "input"))
      (node (ref "JP3D") (pin "3") (pinfunction "3_3") (pintype "passive"))
      (node (ref "U11") (pin "10") (pinfunction "A1_10") (pintype "bidirectional"))
      (node (ref "U43") (pin "14") (pinfunction "RS1_14") (pintype "bidirectional"))
      (node (ref "U51") (pin "37") (pinfunction "RS1_37") (pintype "bidirectional"))
      (node (ref "U61") (pin "37") (pinfunction "RS1_37") (pintype "bidirectional"))
      (node (ref "ZX1-28C256") (pin "9") (pinfunction "9_9") (pintype "passive"))
    )
    (net (code "3") (name "A2") (class "Default")
      (node (ref "IC21") (pin "8") (pinfunction "A2_8") (pintype "input"))
      (node (ref "JP3D") (pin "2") (pinfunction "2_2") (pintype "passive"))
      (node (ref "U11") (pin "11") (pinfunction "A2_11") (pintype "bidirectional"))
      (node (ref "U51") (pin "36") (pinfunction "RS2_36") (pintype "bidirectional"))
      (node (ref "U61") (pin "36") (pinfunction "RS2_36") (pintype "bidirectional"))
      (node (ref "ZX1-28C256") (pin "8") (pinfunction "8_8") (pintype "passive"))
    )
    (net (code "4") (name "A3") (class "Default")
      (node (ref "IC21") (pin "7") (pinfunction "A3_7") (pintype "input"))
      (node (ref "JP3D") (pin "1") (pinfunction "1_1") (pintype "passive"))
      (node (ref "U11") (pin "12") (pinfunction "A3_12") (pintype "bidirectional"))
      (node (ref "U51") (pin "35") (pinfunction "RS3_35") (pintype "bidirectional"))
      (node (ref "U61") (pin "35") (pinfunction "RS3_35") (pintype "bidirectional"))
      (node (ref "ZX1-28C256") (pin "7") (pinfunction "7_7") (pintype "passive"))
    )
    (net (code "5") (name "A4") (class "Default")
      (node (ref "IC21") (pin "6") (pinfunction "A4_6") (pintype "input"))
      (node (ref "IC56") (pin "1") (pinfunction "A_1") (pintype "input"))
      (node (ref "JP3C") (pin "4") (pinfunction "4_4") (pintype "passive"))
      (node (ref "U11") (pin "13") (pinfunction "A4_13") (pintype "bidirectional"))
      (node (ref "ZX1-28C256") (pin "6") (pinfunction "6_6") (pintype "passive"))
    )
    (net (code "6") (name "A5") (class "Default")
      (node (ref "IC21") (pin "5") (pinfunction "A5_5") (pintype "input"))
      (node (ref "IC56") (pin "2") (pinfunction "B_2") (pintype "input"))
      (node (ref "JP3C") (pin "3") (pinfunction "3_3") (pintype "passive"))
      (node (ref "U11") (pin "14") (pinfunction "A5_14") (pintype "bidirectional"))
      (node (ref "ZX1-28C256") (pin "5") (pinfunction "5_5") (pintype "passive"))
    )
    (net (code "7") (name "A6") (class "Default")
      (node (ref "IC21") (pin "4") (pinfunction "A6_4") (pintype "input"))
      (node (ref "IC56") (pin "3") (pinfunction "C_3") (pintype "input"))
      (node (ref "JP3C") (pin "2") (pinfunction "2_2") (pintype "passive"))
      (node (ref "U11") (pin "15") (pinfunction "A6_15") (pintype "bidirectional"))
      (node (ref "ZX1-28C256") (pin "4") (pinfunction "4_4") (pintype "passive"))
    )
    (net (code "8") (name "A7") (class "Default")
      (node (ref "IC21") (pin "3") (pinfunction "A7_3") (pintype "input"))
      (node (ref "IC56") (pin "6") (pinfunction "G1_6") (pintype "input"))
      (node (ref "JP3C") (pin "1") (pinfunction "1_1") (pintype "passive"))
      (node (ref "U11") (pin "16") (pinfunction "A7_16") (pintype "bidirectional"))
      (node (ref "ZX1-28C256") (pin "3") (pinfunction "3_3") (pintype "passive"))
    )
    (net (code "9") (name "A8") (class "Default")
      (node (ref "IC21") (pin "25") (pinfunction "A8_25") (pintype "input"))
      (node (ref "IC55") (pin "6") (pinfunction "G1_6") (pintype "input"))
      (node (ref "IC63") (pin "6") (pinfunction "G1_6") (pintype "input"))
      (node (ref "JP3B") (pin "4") (pinfunction "4_4") (pintype "passive"))
      (node (ref "U11") (pin "17") (pinfunction "A8_17") (pintype "bidirectional"))
      (node (ref "ZX1-28C256") (pin "25") (pinfunction "25_25") (pintype "passive"))
    )
    (net (code "10") (name "A9") (class "Default")
      (node (ref "IC21") (pin "24") (pinfunction "A9_24") (pintype "input"))
      (node (ref "IC55") (pin "3") (pinfunction "C_3") (pintype "input"))
      (node (ref "IC63") (pin "3") (pinfunction "C_3") (pintype "input"))
      (node (ref "JP3B") (pin "3") (pinfunction "3_3") (pintype "passive"))
      (node (ref "U11") (pin "18") (pinfunction "A9_18") (pintype "bidirectional"))
      (node (ref "ZX1-28C256") (pin "24") (pinfunction "24_24") (pintype "passive"))
    )
    (net (code "11") (name "A10") (class "Default")
      (node (ref "IC21") (pin "21") (pinfunction "A10_21") (pintype "input"))
      (node (ref "IC55") (pin "2") (pinfunction "B_2") (pintype "input"))
      (node (ref "IC63") (pin "2") (pinfunction "B_2") (pintype "input"))
      (node (ref "JP3B") (pin "2") (pinfunction "2_2") (pintype "passive"))
      (node (ref "U11") (pin "19") (pinfunction "A10_19") (pintype "bidirectional"))
      (node (ref "ZX1-28C256") (pin "21") (pinfunction "21_21") (pintype "passive"))
    )
    (net (code "12") (name "A11") (class "Default")
      (node (ref "IC21") (pin "23") (pinfunction "A11_23") (pintype "input"))
      (node (ref "IC55") (pin "1") (pinfunction "A_1") (pintype "input"))
      (node (ref "IC63") (pin "1") (pinfunction "A_1") (pintype "input"))
      (node (ref "JP3B") (pin "1") (pinfunction "1_1") (pintype "passive"))
      (node (ref "U11") (pin "20") (pinfunction "A11_20") (pintype "bidirectional"))
      (node (ref "ZX1-28C256") (pin "23") (pinfunction "23_23") (pintype "passive"))
    )
    (net (code "13") (name "A12") (class "Default")
      (node (ref "IC21") (pin "2") (pinfunction "A12_2") (pintype "input"))
      (node (ref "IC22") (pin "1") (pinfunction "A_1") (pintype "input"))
      (node (ref "IC32") (pin "1") (pinfunction "A_1") (pintype "input"))
      (node (ref "IC42") (pin "1") (pinfunction "A_1") (pintype "input"))
      (node (ref "IC54") (pin "1") (pinfunction "A_1") (pintype "input"))
      (node (ref "JP3A") (pin "4") (pinfunction "4_4") (pintype "passive"))
      (node (ref "U11") (pin "22") (pinfunction "A12_22") (pintype "bidirectional"))
      (node (ref "U51") (pin "24") (pinfunction "CS1_24") (pintype "bidirectional"))
      (node (ref "ZX1-28C256") (pin "2") (pinfunction "2_2") (pintype "passive"))
    )
    (net (code "14") (name "A13") (class "Default")
      (node (ref "IC21") (pin "26") (pinfunction "A13_26") (pintype "input"))
      (node (ref "IC22") (pin "2") (pinfunction "B_2") (pintype "input"))
      (node (ref "IC32") (pin "2") (pinfunction "B_2") (pintype "input"))
      (node (ref "IC42") (pin "2") (pinfunction "B_2") (pintype "input"))
      (node (ref "IC54") (pin "2") (pinfunction "B_2") (pintype "input"))
      (node (ref "JP3A") (pin "3") (pinfunction "3_3") (pintype "passive"))
      (node (ref "U11") (pin "23") (pinfunction "A13_23") (pintype "bidirectional"))
      (node (ref "ZX1-28C256") (pin "26") (pinfunction "26_26") (pintype "passive"))
    )
    (net (code "15") (name "A14") (class "Default")
      (node (ref "IC21") (pin "1") (pinfunction "A14_1") (pintype "input"))
      (node (ref "IC22") (pin "3") (pinfunction "C_3") (pintype "input"))
      (node (ref "IC32") (pin "3") (pinfunction "C_3") (pintype "input"))
      (node (ref "IC42") (pin "3") (pinfunction "C_3") (pintype "input"))
      (node (ref "IC54") (pin "3") (pinfunction "C_3") (pintype "input"))
      (node (ref "JP3A") (pin "2") (pinfunction "2_2") (pintype "passive"))
      (node (ref "U11") (pin "24") (pinfunction "A14_24") (pintype "bidirectional"))
      (node (ref "U43") (pin "2") (pinfunction "CS0_2") (pintype "bidirectional"))
      (node (ref "U61") (pin "24") (pinfunction "CS1_24") (pintype "bidirectional"))
      (node (ref "ZX1-28C256") (pin "1") (pinfunction "1_1") (pintype "passive"))
    )
    (net (code "16") (name "A15") (class "Default")
      (node (ref "IC25") (pin "1") (pinfunction "I0_1") (pintype "input"))
      (node (ref "IC25") (pin "2") (pinfunction "I1_2") (pintype "input"))
      (node (ref "IC32") (pin "6") (pinfunction "G1_6") (pintype "input"))
      (node (ref "IC42") (pin "6") (pinfunction "G1_6") (pintype "input"))
      (node (ref "IC54") (pin "6") (pinfunction "G1_6") (pintype "input"))
      (node (ref "JP3A") (pin "1") (pinfunction "1_1") (pintype "passive"))
      (node (ref "U11") (pin "25") (pinfunction "A15_25") (pintype "bidirectional"))
    )
    (net (code "17") (name "BE") (class "Default")
      (node (ref "R18") (pin "1") (pinfunction "1_1") (pintype "passive"))
      (node (ref "U11") (pin "36") (pinfunction "BE_36") (pintype "bidirectional"))
    )
    (net (code "18") (name "CS0_RAM") (class "Default")
      (node (ref "IC22") (pin "15") (pinfunction "Y0_15") (pintype "output"))
      (node (ref "IC23") (pin "1") (pinfunction "I0_1") (pintype "input"))
    )
    (net (code "19") (name "CS0_ROM") (class "Default")
      (node (ref "IC32") (pin "15") (pinfunction "Y0_15") (pintype "output"))
      (node (ref "IC33") (pin "1") (pinfunction "I0_1") (pintype "input"))
    )
    (net (code "20") (name "CS1_RAM") (class "Default")
      (node (ref "IC22") (pin "14") (pinfunction "Y1_14") (pintype "output"))
      (node (ref "IC23") (pin "2") (pinfunction "I1_2") (pintype "input"))
    )
    (net (code "21") (name "CS1_ROM") (class "Default")
      (node (ref "IC32") (pin "14") (pinfunction "Y1_14") (pintype "output"))
      (node (ref "IC33") (pin "2") (pinfunction "I1_2") (pintype "input"))
    )
    (net (code "22") (name "CS2_RAM") (class "Default")
      (node (ref "IC22") (pin "13") (pinfunction "Y2_13") (pintype "output"))
      (node (ref "IC23") (pin "4") (pinfunction "I0_4") (pintype "input"))
    )
    (net (code "23") (name "CS2_ROM") (class "Default")
      (node (ref "IC32") (pin "13") (pinfunction "Y2_13") (pintype "output"))
      (node (ref "IC33") (pin "4") (pinfunction "I0_4") (pintype "input"))
    )
    (net (code "24") (name "CS3_RAM") (class "Default")
      (node (ref "IC22") (pin "12") (pinfunction "Y3_12") (pintype "output"))
      (node (ref "IC23") (pin "5") (pinfunction "I1_5") (pintype "input"))
    )
    (net (code "25") (name "CS3_ROM") (class "Default")
      (node (ref "IC32") (pin "12") (pinfunction "Y3_12") (pintype "output"))
      (node (ref "IC33") (pin "5") (pinfunction "I1_5") (pintype "input"))
    )
    (net (code "26") (name "CS4_RAM") (class "Default")
      (node (ref "IC22") (pin "11") (pinfunction "Y4_11") (pintype "output"))
      (node (ref "IC23") (pin "9") (pinfunction "I0_9") (pintype "input"))
    )
    (net (code "27") (name "CS5_RAM") (class "Default")
      (node (ref "IC22") (pin "10") (pinfunction "Y5_10") (pintype "output"))
      (node (ref "IC23") (pin "10") (pinfunction "I1_10") (pintype "input"))
    )
    (net (code "28") (name "CS6_RAM") (class "Default")
      (node (ref "IC22") (pin "9") (pinfunction "Y6_9") (pintype "output"))
      (node (ref "IC23") (pin "12") (pinfunction "I0_12") (pintype "input"))
    )
    (net (code "29") (name "CS6_ROM") (class "Default")
      (node (ref "IC32") (pin "9") (pinfunction "Y6_9") (pintype "output"))
      (node (ref "IC33") (pin "12") (pinfunction "I0_12") (pintype "input"))
    )
    (net (code "30") (name "CS7_RAM") (class "Default")
      (node (ref "IC22") (pin "7") (pinfunction "Y7_7") (pintype "output"))
      (node (ref "IC23") (pin "13") (pinfunction "I1_13") (pintype "input"))
    )
    (net (code "31") (name "CS7_ROM") (class "Default")
      (node (ref "IC32") (pin "7") (pinfunction "Y7_7") (pintype "output"))
      (node (ref "IC33") (pin "13") (pinfunction "I1_13") (pintype "input"))
    )
    (net (code "32") (name "CS_RAM") (class "Default")
      (node (ref "IC21") (pin "20") (pinfunction "~{CS}_20") (pintype "input"))
      (node (ref "IC24") (pin "8") (pinfunction "O_8") (pintype "output"))
    )
    (net (code "33") (name "CS_ROM") (class "Default")
      (node (ref "IC34") (pin "8") (pinfunction "O_8") (pintype "output"))
      (node (ref "ZX1-28C256") (pin "20") (pinfunction "20_20") (pintype "passive"))
      (node (ref "ZX1-28C256") (pin "22") (pinfunction "22_22") (pintype "passive"))
    )
    (net (code "34") (name "D0") (class "Default")
      (node (ref "IC21") (pin "11") (pinfunction "I/O0_11") (pintype "bidirectional"))
      (node (ref "JP2B") (pin "4") (pinfunction "4_4") (pintype "passive"))
      (node (ref "U11") (pin "33") (pinfunction "D0_33") (pintype "bidirectional"))
      (node (ref "U43") (pin "18") (pinfunction "DB0_18") (pintype "bidirectional"))
      (node (ref "U51") (pin "33") (pinfunction "D0_33") (pintype "bidirectional"))
      (node (ref "U61") (pin "33") (pinfunction "D0_33") (pintype "bidirectional"))
      (node (ref "ZX1-28C256") (pin "11") (pinfunction "11_11") (pintype "passive"))
    )
    (net (code "35") (name "D1") (class "Default")
      (node (ref "IC21") (pin "12") (pinfunction "I/O1_12") (pintype "bidirectional"))
      (node (ref "JP2B") (pin "3") (pinfunction "3_3") (pintype "passive"))
      (node (ref "U11") (pin "32") (pinfunction "D1_32") (pintype "bidirectional"))
      (node (ref "U43") (pin "19") (pinfunction "DB1_19") (pintype "bidirectional"))
      (node (ref "U51") (pin "32") (pinfunction "D1_32") (pintype "bidirectional"))
      (node (ref "U61") (pin "32") (pinfunction "D1_32") (pintype "bidirectional"))
      (node (ref "ZX1-28C256") (pin "12") (pinfunction "12_12") (pintype "passive"))
    )
    (net (code "36") (name "D2") (class "Default")
      (node (ref "IC21") (pin "13") (pinfunction "I/O2_13") (pintype "bidirectional"))
      (node (ref "JP2B") (pin "2") (pinfunction "2_2") (pintype "passive"))
      (node (ref "U11") (pin "31") (pinfunction "D2_31") (pintype "bidirectional"))
      (node (ref "U43") (pin "20") (pinfunction "DB2_20") (pintype "bidirectional"))
      (node (ref "U51") (pin "31") (pinfunction "D2_31") (pintype "bidirectional"))
      (node (ref "U61") (pin "31") (pinfunction "D2_31") (pintype "bidirectional"))
      (node (ref "ZX1-28C256") (pin "13") (pinfunction "13_13") (pintype "passive"))
    )
    (net (code "37") (name "D3") (class "Default")
      (node (ref "IC21") (pin "15") (pinfunction "I/O3_15") (pintype "bidirectional"))
      (node (ref "JP2B") (pin "1") (pinfunction "1_1") (pintype "passive"))
      (node (ref "U11") (pin "30") (pinfunction "D3_30") (pintype "bidirectional"))
      (node (ref "U43") (pin "21") (pinfunction "DB3_21") (pintype "bidirectional"))
      (node (ref "U51") (pin "30") (pinfunction "D3_30") (pintype "bidirectional"))
      (node (ref "U61") (pin "30") (pinfunction "D3_30") (pintype "bidirectional"))
      (node (ref "ZX1-28C256") (pin "15") (pinfunction "15_15") (pintype "passive"))
    )
    (net (code "38") (name "D4") (class "Default")
      (node (ref "IC21") (pin "16") (pinfunction "I/O4_16") (pintype "bidirectional"))
      (node (ref "JP2A") (pin "4") (pinfunction "4_4") (pintype "passive"))
      (node (ref "U11") (pin "29") (pinfunction "D4_29") (pintype "bidirectional"))
      (node (ref "U43") (pin "22") (pinfunction "DB4_22") (pintype "bidirectional"))
      (node (ref "U51") (pin "29") (pinfunction "D4_29") (pintype "bidirectional"))
      (node (ref "U61") (pin "29") (pinfunction "D4_29") (pintype "bidirectional"))
      (node (ref "ZX1-28C256") (pin "16") (pinfunction "16_16") (pintype "passive"))
    )
    (net (code "39") (name "D5") (class "Default")
      (node (ref "IC21") (pin "17") (pinfunction "I/O5_17") (pintype "bidirectional"))
      (node (ref "JP2A") (pin "3") (pinfunction "3_3") (pintype "passive"))
      (node (ref "U11") (pin "28") (pinfunction "D5_28") (pintype "bidirectional"))
      (node (ref "U43") (pin "23") (pinfunction "DB5_23") (pintype "bidirectional"))
      (node (ref "U51") (pin "28") (pinfunction "D5_28") (pintype "bidirectional"))
      (node (ref "U61") (pin "28") (pinfunction "D5_28") (pintype "bidirectional"))
      (node (ref "ZX1-28C256") (pin "17") (pinfunction "17_17") (pintype "passive"))
    )
    (net (code "40") (name "D6") (class "Default")
      (node (ref "IC21") (pin "18") (pinfunction "I/O6_18") (pintype "bidirectional"))
      (node (ref "JP2A") (pin "2") (pinfunction "2_2") (pintype "passive"))
      (node (ref "U11") (pin "27") (pinfunction "D6_27") (pintype "bidirectional"))
      (node (ref "U43") (pin "24") (pinfunction "DB6_24") (pintype "bidirectional"))
      (node (ref "U51") (pin "27") (pinfunction "D6_27") (pintype "bidirectional"))
      (node (ref "U61") (pin "27") (pinfunction "D6_27") (pintype "bidirectional"))
      (node (ref "ZX1-28C256") (pin "18") (pinfunction "18_18") (pintype "passive"))
    )
    (net (code "41") (name "D7") (class "Default")
      (node (ref "IC21") (pin "19") (pinfunction "I/O7_19") (pintype "bidirectional"))
      (node (ref "JP2A") (pin "1") (pinfunction "1_1") (pintype "passive"))
      (node (ref "U11") (pin "26") (pinfunction "D7_26") (pintype "bidirectional"))
      (node (ref "U43") (pin "25") (pinfunction "DB7_25") (pintype "bidirectional"))
      (node (ref "U51") (pin "26") (pinfunction "D7_26") (pintype "bidirectional"))
      (node (ref "U61") (pin "26") (pinfunction "D7_26") (pintype "bidirectional"))
      (node (ref "ZX1-28C256") (pin "19") (pinfunction "19_19") (pintype "passive"))
    )
    (net (code "42") (name "EN") (class "Default")
      (node (ref "IC22") (pin "6") (pinfunction "G1_6") (pintype "input"))
      (node (ref "IC25") (pin "3") (pinfunction "O_3") (pintype "output"))
    )
    (net (code "43") (name "GND") (class "Default")
      (node (ref "C11") (pin "1") (pinfunction "1_1") (pintype "passive"))
      (node (ref "C12") (pin "-") (pinfunction "-_-") (pintype "passive"))
      (node (ref "C13") (pin "1") (pinfunction "1_1") (pintype "passive"))
      (node (ref "C14") (pin "1") (pinfunction "1_1") (pintype "passive"))
      (node (ref "C15") (pin "1") (pinfunction "1_1") (pintype "passive"))
      (node (ref "C21") (pin "1") (pinfunction "1_1") (pintype "passive"))
      (node (ref "C22") (pin "1") (pinfunction "1_1") (pintype "passive"))
      (node (ref "C23") (pin "1") (pinfunction "1_1") (pintype "passive"))
      (node (ref "C24") (pin "1") (pinfunction "1_1") (pintype "passive"))
      (node (ref "C25") (pin "1") (pinfunction "1_1") (pintype "passive"))
      (node (ref "C31") (pin "1") (pinfunction "1_1") (pintype "passive"))
      (node (ref "C32") (pin "1") (pinfunction "1_1") (pintype "passive"))
      (node (ref "C33") (pin "1") (pinfunction "1_1") (pintype "passive"))
      (node (ref "C34") (pin "1") (pinfunction "1_1") (pintype "passive"))
      (node (ref "C43") (pin "2") (pinfunction "2_2") (pintype "passive"))
      (node (ref "C44") (pin "2") (pinfunction "2_2") (pintype "passive"))
      (node (ref "C45") (pin "1") (pinfunction "1_1") (pintype "passive"))
      (node (ref "C46") (pin "1") (pinfunction "1_1") (pintype "passive"))
      (node (ref "C47") (pin "1") (pinfunction "1_1") (pintype "passive"))
      (node (ref "C48") (pin "1") (pinfunction "1_1") (pintype "passive"))
      (node (ref "C51") (pin "1") (pinfunction "1_1") (pintype "passive"))
      (node (ref "C52") (pin "1") (pinfunction "1_1") (pintype "passive"))
      (node (ref "C53") (pin "1") (pinfunction "1_1") (pintype "passive"))
      (node (ref "C54") (pin "1") (pinfunction "1_1") (pintype "passive"))
      (node (ref "C55") (pin "1") (pinfunction "1_1") (pintype "passive"))
      (node (ref "C56") (pin "1") (pinfunction "1_1") (pintype "passive"))
      (node (ref "C57") (pin "1") (pinfunction "1_1") (pintype "passive"))
      (node (ref "C61") (pin "1") (pinfunction "1_1") (pintype "passive"))
      (node (ref "C63") (pin "1") (pinfunction "1_1") (pintype "passive"))
      (node (ref "IC12") (pin "1") (pinfunction "GND_1") (pintype "power_in"))
      (node (ref "IC13") (pin "11") (pinfunction "I_11") (pintype "input"))
      (node (ref "IC13") (pin "13") (pinfunction "I_13") (pintype "input"))
      (node (ref "IC13") (pin "3") (pinfunction "I_3") (pintype "input"))
      (node (ref "IC13") (pin "5") (pinfunction "I_5") (pintype "input"))
      (node (ref "IC13") (pin "7") (pinfunction "GND_7") (pintype "power_in"))
      (node (ref "IC13") (pin "9") (pinfunction "I_9") (pintype "input"))
      (node (ref "IC21") (pin "14") (pinfunction "VSS_14") (pintype "power_in"))
      (node (ref "IC22") (pin "4") (pinfunction "G2A_4") (pintype "input"))
      (node (ref "IC22") (pin "5") (pinfunction "G2B_5") (pintype "input"))
      (node (ref "IC22") (pin "8") (pinfunction "GND_8") (pintype "power_in"))
      (node (ref "IC23") (pin "7") (pinfunction "GND_7") (pintype "power_in"))
      (node (ref "IC24") (pin "12") (pinfunction "I0_12") (pintype "input"))
      (node (ref "IC24") (pin "13") (pinfunction "I1_13") (pintype "input"))
      (node (ref "IC24") (pin "7") (pinfunction "GND_7") (pintype "power_in"))
      (node (ref "IC25") (pin "7") (pinfunction "GND_7") (pintype "power_in"))
      (node (ref "IC32") (pin "4") (pinfunction "G2A_4") (pintype "input"))
      (node (ref "IC32") (pin "5") (pinfunction "G2B_5") (pintype "input"))
      (node (ref "IC32") (pin "8") (pinfunction "GND_8") (pintype "power_in"))
      (node (ref "IC33") (pin "7") (pinfunction "GND_7") (pintype "power_in"))
      (node (ref "IC34") (pin "12") (pinfunction "I0_12") (pintype "input"))
      (node (ref "IC34") (pin "13") (pinfunction "I1_13") (pintype "input"))
      (node (ref "IC34") (pin "7") (pinfunction "GND_7") (pintype "power_in"))
      (node (ref "IC41") (pin "15") (pinfunction "GND_15") (pintype "power_in"))
      (node (ref "IC42") (pin "4") (pinfunction "G2A_4") (pintype "input"))
      (node (ref "IC42") (pin "5") (pinfunction "G2B_5") (pintype "input"))
      (node (ref "IC42") (pin "8") (pinfunction "GND_8") (pintype "power_in"))
      (node (ref "IC52") (pin "13") (pinfunction "G_13") (pintype "input"))
      (node (ref "IC52") (pin "8") (pinfunction "GND_8") (pintype "power_in"))
      (node (ref "IC53") (pin "13") (pinfunction "G_13") (pintype "input"))
      (node (ref "IC53") (pin "8") (pinfunction "GND_8") (pintype "power_in"))
      (node (ref "IC54") (pin "4") (pinfunction "G2A_4") (pintype "input"))
      (node (ref "IC54") (pin "5") (pinfunction "G2B_5") (pintype "input"))
      (node (ref "IC54") (pin "8") (pinfunction "GND_8") (pintype "power_in"))
      (node (ref "IC55") (pin "8") (pinfunction "GND_8") (pintype "power_in"))
      (node (ref "IC56") (pin "4") (pinfunction "G2A_4") (pintype "input"))
      (node (ref "IC56") (pin "5") (pinfunction "G2B_5") (pintype "input"))
      (node (ref "IC56") (pin "8") (pinfunction "GND_8") (pintype "power_in"))
      (node (ref "IC57") (pin "1") (pinfunction "I_1") (pintype "input"))
      (node (ref "IC57") (pin "3") (pinfunction "I_3") (pintype "input"))
      (node (ref "IC57") (pin "5") (pinfunction "I_5") (pintype "input"))
      (node (ref "IC57") (pin "7") (pinfunction "GND_7") (pintype "power_in"))
      (node (ref "IC63") (pin "8") (pinfunction "GND_8") (pintype "power_in"))
      (node (ref "J1") (pin "1") (pinfunction "1_1") (pintype "passive"))
      (node (ref "JP1") (pin "2") (pinfunction "2_2") (pintype "passive"))
      (node (ref "JP13") (pin "1") (pinfunction "1_1") (pintype "passive"))
      (node (ref "LCD1") (pin "24") (pinfunction "LEDK_24") (pintype "power_in"))
      (node (ref "LCD1") (pin "3") (pinfunction "FG_3") (pintype "input"))
      (node (ref "LCD1") (pin "4") (pinfunction "VSS_4") (pintype "power_in"))
      (node (ref "QG1") (pin "7") (pinfunction "GND_7") (pintype "power_in"))
      (node (ref "R1") (pin "1") (pinfunction "1_1") (pintype "passive"))
      (node (ref "R61") (pin "2") (pinfunction "2_2") (pintype "passive"))
      (node (ref "SW1") (pin "1") (pinfunction "1_1") (pintype "passive"))
      (node (ref "U11") (pin "21") (pinfunction "GND_21") (pintype "power_in"))
      (node (ref "U43") (pin "1") (pinfunction "GND_1") (pintype "bidirectional"))
      (node (ref "U43") (pin "16") (pinfunction "~{DCD}_16") (pintype "bidirectional"))
      (node (ref "U43") (pin "17") (pinfunction "~{DSR}_17") (pintype "bidirectional"))
      (node (ref "U43") (pin "9") (pinfunction "~{CTS}_9") (pintype "bidirectional"))
      (node (ref "U51") (pin "1") (pinfunction "GND_1") (pintype "bidirectional"))
      (node (ref "U61") (pin "1") (pinfunction "GND_1") (pintype "bidirectional"))
      (node (ref "X1") (pin "5") (pinfunction "5_5") (pintype "passive"))
      (node (ref "X2") (pin "4") (pinfunction "4_4") (pintype "passive"))
      (node (ref "X2") (pin "PE") (pinfunction "PE_PE") (pintype "power_in"))
      (node (ref "X2") (pin "PE@") (pinfunction "PE_PE@") (pintype "power_in"))
      (node (ref "ZX1-28C256") (pin "14") (pinfunction "14_14") (pintype "passive"))
    )
    (net (code "44") (name "KB_CLK") (class "Default")
      (node (ref "IC57") (pin "11") (pinfunction "I_11") (pintype "input"))
      (node (ref "IC57") (pin "13") (pinfunction "I_13") (pintype "input"))
      (node (ref "X2") (pin "1") (pinfunction "1_1") (pintype "passive"))
    )
    (net (code "45") (name "KB_DATA") (class "Default")
      (node (ref "IC52") (pin "14") (pinfunction "SER_14") (pintype "input"))
      (node (ref "X2") (pin "2") (pinfunction "2_2") (pintype "passive"))
    )
    (net (code "46") (name "KB_INT") (class "Default")
      (node (ref "IC52") (pin "12") (pinfunction "RCK_12") (pintype "input"))
      (node (ref "IC53") (pin "12") (pinfunction "RCK_12") (pintype "input"))
      (node (ref "IC57") (pin "8") (pinfunction "O_8") (pintype "output"))
      (node (ref "U51") (pin "40") (pinfunction "CA1_40") (pintype "bidirectional"))
    )
    (net (code "47") (name "Net-(IC12-DIS)") (class "Default")
      (node (ref "C12") (pin "+") (pinfunction "+_+") (pintype "passive"))
      (node (ref "IC12") (pin "6") (pinfunction "TRE_6") (pintype "input"))
      (node (ref "IC12") (pin "7") (pinfunction "DIS_7") (pintype "input"))
      (node (ref "R12") (pin "1") (pinfunction "1_1") (pintype "passive"))
    )
    (net (code "48") (name "Net-(IC12-OUT)") (class "Default")
      (node (ref "IC12") (pin "3") (pinfunction "OUT_3") (pintype "output"))
      (node (ref "IC13") (pin "1") (pinfunction "I_1") (pintype "input"))
    )
    (net (code "49") (name "Net-(IC12-TRI)") (class "Default")
      (node (ref "C11") (pin "2") (pinfunction "2_2") (pintype "passive"))
      (node (ref "IC12") (pin "2") (pinfunction "TRI_2") (pintype "input"))
      (node (ref "R11") (pin "1") (pinfunction "1_1") (pintype "passive"))
      (node (ref "SW1") (pin "2") (pinfunction "2_2") (pintype "passive"))
    )
    (net (code "50") (name "Net-(IC23A-O)") (class "Default")
      (node (ref "IC23") (pin "3") (pinfunction "O_3") (pintype "output"))
      (node (ref "IC24") (pin "1") (pinfunction "I0_1") (pintype "input"))
    )
    (net (code "51") (name "Net-(IC23B-O)") (class "Default")
      (node (ref "IC23") (pin "6") (pinfunction "O_6") (pintype "output"))
      (node (ref "IC24") (pin "2") (pinfunction "I1_2") (pintype "input"))
    )
    (net (code "52") (name "Net-(IC23C-O)") (class "Default")
      (node (ref "IC23") (pin "8") (pinfunction "O_8") (pintype "output"))
      (node (ref "IC24") (pin "4") (pinfunction "I0_4") (pintype "input"))
    )
    (net (code "53") (name "Net-(IC23D-O)") (class "Default")
      (node (ref "IC23") (pin "11") (pinfunction "O_11") (pintype "output"))
      (node (ref "IC24") (pin "5") (pinfunction "I1_5") (pintype "input"))
    )
    (net (code "54") (name "Net-(IC24A-O)") (class "Default")
      (node (ref "IC24") (pin "3") (pinfunction "O_3") (pintype "output"))
      (node (ref "IC24") (pin "9") (pinfunction "I0_9") (pintype "input"))
    )
    (net (code "55") (name "Net-(IC24B-O)") (class "Default")
      (node (ref "IC24") (pin "10") (pinfunction "I1_10") (pintype "input"))
      (node (ref "IC24") (pin "6") (pinfunction "O_6") (pintype "output"))
    )
    (net (code "56") (name "Net-(IC25B-I1)") (class "Default")
      (node (ref "IC25") (pin "11") (pinfunction "O_11") (pintype "output"))
      (node (ref "IC25") (pin "5") (pinfunction "I1_5") (pintype "input"))
    )
    (net (code "57") (name "Net-(IC33A-O)") (class "Default")
      (node (ref "IC33") (pin "3") (pinfunction "O_3") (pintype "output"))
      (node (ref "IC34") (pin "1") (pinfunction "I0_1") (pintype "input"))
    )
    (net (code "58") (name "Net-(IC33B-O)") (class "Default")
      (node (ref "IC33") (pin "6") (pinfunction "O_6") (pintype "output"))
      (node (ref "IC34") (pin "2") (pinfunction "I1_2") (pintype "input"))
    )
    (net (code "59") (name "Net-(IC33C-O)") (class "Default")
      (node (ref "IC33") (pin "8") (pinfunction "O_8") (pintype "output"))
      (node (ref "IC34") (pin "4") (pinfunction "I0_4") (pintype "input"))
    )
    (net (code "60") (name "Net-(IC33D-O)") (class "Default")
      (node (ref "IC33") (pin "11") (pinfunction "O_11") (pintype "output"))
      (node (ref "IC34") (pin "5") (pinfunction "I1_5") (pintype "input"))
    )
    (net (code "61") (name "Net-(IC34A-O)") (class "Default")
      (node (ref "IC34") (pin "3") (pinfunction "O_3") (pintype "output"))
      (node (ref "IC34") (pin "9") (pinfunction "I0_9") (pintype "input"))
    )
    (net (code "62") (name "Net-(IC34B-O)") (class "Default")
      (node (ref "IC34") (pin "10") (pinfunction "I1_10") (pintype "input"))
      (node (ref "IC34") (pin "6") (pinfunction "O_6") (pintype "output"))
    )
    (net (code "63") (name "Net-(IC41A-C1+)") (class "Default")
      (node (ref "C41") (pin "2") (pinfunction "2_2") (pintype "passive"))
      (node (ref "IC41") (pin "1") (pinfunction "C1+_1") (pintype "bidirectional"))
    )
    (net (code "64") (name "Net-(IC41A-C1-)") (class "Default")
      (node (ref "C41") (pin "1") (pinfunction "1_1") (pintype "passive"))
      (node (ref "IC41") (pin "3") (pinfunction "C1-_3") (pintype "bidirectional"))
    )
    (net (code "65") (name "Net-(IC41A-C2+)") (class "Default")
      (node (ref "C42") (pin "2") (pinfunction "2_2") (pintype "passive"))
      (node (ref "IC41") (pin "4") (pinfunction "C2+_4") (pintype "bidirectional"))
    )
    (net (code "66") (name "Net-(IC41A-C2-)") (class "Default")
      (node (ref "C42") (pin "1") (pinfunction "1_1") (pintype "passive"))
      (node (ref "IC41") (pin "5") (pinfunction "C2-_5") (pintype "bidirectional"))
    )
    (net (code "67") (name "Net-(IC41A-R1IN)") (class "Default")
      (node (ref "IC41") (pin "13") (pinfunction "R1IN_13") (pintype "input"))
      (node (ref "X1") (pin "3") (pinfunction "3_3") (pintype "passive"))
    )
    (net (code "68") (name "Net-(IC41A-T1OUT)") (class "Default")
      (node (ref "IC41") (pin "14") (pinfunction "T1OUT_14") (pintype "output"))
      (node (ref "X1") (pin "2") (pinfunction "2_2") (pintype "passive"))
    )
    (net (code "69") (name "Net-(IC41A-V+)") (class "Default")
      (node (ref "C43") (pin "1") (pinfunction "1_1") (pintype "passive"))
      (node (ref "IC41") (pin "2") (pinfunction "V+_2") (pintype "bidirectional"))
    )
    (net (code "70") (name "Net-(IC41A-V-)") (class "Default")
      (node (ref "C44") (pin "1") (pinfunction "1_1") (pintype "passive"))
      (node (ref "IC41") (pin "6") (pinfunction "V-_6") (pintype "bidirectional"))
    )
    (net (code "71") (name "Net-(IC52A-QH*)") (class "Default")
      (node (ref "IC52") (pin "9") (pinfunction "QH*_9") (pintype "tri_state"))
      (node (ref "IC53") (pin "14") (pinfunction "SER_14") (pintype "input"))
    )
    (net (code "72") (name "Net-(IC57B-O)") (class "Default")
      (node (ref "D52") (pin "A") (pinfunction "A_A") (pintype "passive"))
      (node (ref "IC57") (pin "10") (pinfunction "O_10") (pintype "output"))
      (node (ref "R51") (pin "2") (pinfunction "2_2") (pintype "passive"))
    )
    (net (code "73") (name "Net-(IC57C-I)") (class "Default")
      (node (ref "C51") (pin "2") (pinfunction "2_2") (pintype "passive"))
      (node (ref "D52") (pin "C") (pinfunction "C_C") (pintype "passive"))
      (node (ref "IC57") (pin "9") (pinfunction "I_9") (pintype "input"))
      (node (ref "R51") (pin "1") (pinfunction "1_1") (pintype "passive"))
    )
    (net (code "74") (name "Net-(LCD1-LEDA)") (class "Default")
      (node (ref "LCD1") (pin "23") (pinfunction "LEDA_23") (pintype "power_in"))
      (node (ref "R62") (pin "2") (pinfunction "2_2") (pintype "passive"))
    )
    (net (code "75") (name "Net-(LCD1-VEE)") (class "Default")
      (node (ref "LCD1") (pin "7") (pinfunction "VEE_7") (pintype "power_in"))
      (node (ref "R61") (pin "1") (pinfunction "1_1") (pintype "passive"))
    )
    (net (code "76") (name "Net-(LCD1-VO)") (class "Default")
      (node (ref "LCD1") (pin "6") (pinfunction "VO_6") (pintype "power_in"))
      (node (ref "R61") (pin "3") (pinfunction "3_3") (pintype "passive"))
    )
    (net (code "77") (name "Net-(LED1-C)") (class "Default")
      (node (ref "LED1") (pin "K") (pinfunction "C_K") (pintype "passive"))
      (node (ref "R1") (pin "2") (pinfunction "2_2") (pintype "passive"))
    )
    (net (code "78") (name "Net-(R31-Pad1)") (class "Default")
      (node (ref "R31") (pin "1") (pinfunction "1_1") (pintype "passive"))
      (node (ref "ZX1-28C256") (pin "27") (pinfunction "27_27") (pintype "passive"))
    )
    (net (code "79") (name "Net-(U11-~{IRQ})") (class "Default")
      (node (ref "JP11") (pin "2") (pinfunction "2_2") (pintype "passive"))
      (node (ref "R15") (pin "2") (pinfunction "2_2") (pintype "passive"))
      (node (ref "U11") (pin "4") (pinfunction "~{IRQ}_4") (pintype "bidirectional"))
    )
    (net (code "80") (name "Net-(U11-~{NMI})") (class "Default")
      (node (ref "JP12") (pin "2") (pinfunction "2_2") (pintype "passive"))
      (node (ref "R16") (pin "2") (pinfunction "2_2") (pintype "passive"))
      (node (ref "U11") (pin "6") (pinfunction "~{NMI}_6") (pintype "bidirectional"))
    )
    (net (code "81") (name "Net-(U43-XTAL1)") (class "Default")
      (node (ref "C45") (pin "2") (pinfunction "2_2") (pintype "passive"))
      (node (ref "Q41") (pin "2") (pinfunction "2_2") (pintype "passive"))
      (node (ref "R41") (pin "2") (pinfunction "2_2") (pintype "passive"))
      (node (ref "U43") (pin "6") (pinfunction "XTAL1_6") (pintype "bidirectional"))
    )
    (net (code "82") (name "Net-(U43-XTAL2)") (class "Default")
      (node (ref "Q41") (pin "1") (pinfunction "1_1") (pintype "passive"))
      (node (ref "R41") (pin "1") (pinfunction "1_1") (pintype "passive"))
      (node (ref "U43") (pin "7") (pinfunction "XTAL2_7") (pintype "bidirectional"))
    )
    (net (code "83") (name "Net-(U43-~{IRQ})") (class "Default")
      (node (ref "D41") (pin "C") (pinfunction "C_C") (pintype "passive"))
      (node (ref "U43") (pin "26") (pinfunction "~{IRQ}_26") (pintype "bidirectional"))
    )
    (net (code "84") (name "Net-(U51-~{IRQ})") (class "Default")
      (node (ref "D51") (pin "C") (pinfunction "C_C") (pintype "passive"))
      (node (ref "U51") (pin "21") (pinfunction "~{IRQ}_21") (pintype "bidirectional"))
    )
    (net (code "85") (name "Net-(U61-~{IRQ})") (class "Default")
      (node (ref "D61") (pin "C") (pinfunction "C_C") (pintype "passive"))
      (node (ref "U61") (pin "21") (pinfunction "~{IRQ}_21") (pintype "bidirectional"))
    )
    (net (code "86") (name "OE") (class "Default")
      (node (ref "IC21") (pin "22") (pinfunction "~{OE}_22") (pintype "input"))
      (node (ref "IC25") (pin "8") (pinfunction "O_8") (pintype "output"))
    )
    (net (code "87") (name "PA05") (class "Default")
      (node (ref "IC53") (pin "1") (pinfunction "QB_1") (pintype "tri_state"))
      (node (ref "U51") (pin "2") (pinfunction "PA0_2") (pintype "bidirectional"))
    )
    (net (code "88") (name "PA06") (class "Default")
      (node (ref "LCD1") (pin "9") (pinfunction "~{RD}_9") (pintype "bidirectional"))
      (node (ref "U61") (pin "2") (pinfunction "PA0_2") (pintype "bidirectional"))
    )
    (net (code "89") (name "PA15") (class "Default")
      (node (ref "IC53") (pin "15") (pinfunction "QA_15") (pintype "tri_state"))
      (node (ref "U51") (pin "3") (pinfunction "PA1_3") (pintype "bidirectional"))
    )
    (net (code "90") (name "PA16") (class "Default")
      (node (ref "LCD1") (pin "8") (pinfunction "~{WR}_8") (pintype "input"))
      (node (ref "U61") (pin "3") (pinfunction "PA1_3") (pintype "bidirectional"))
    )
    (net (code "91") (name "PA25") (class "Default")
      (node (ref "IC52") (pin "7") (pinfunction "QH_7") (pintype "tri_state"))
      (node (ref "U51") (pin "4") (pinfunction "PA2_4") (pintype "bidirectional"))
    )
    (net (code "92") (name "PA26") (class "Default")
      (node (ref "LCD1") (pin "10") (pinfunction "~{CE}_10") (pintype "bidirectional"))
      (node (ref "U61") (pin "4") (pinfunction "PA2_4") (pintype "bidirectional"))
    )
    (net (code "93") (name "PA35") (class "Default")
      (node (ref "IC52") (pin "6") (pinfunction "QG_6") (pintype "tri_state"))
      (node (ref "U51") (pin "5") (pinfunction "PA3_5") (pintype "bidirectional"))
    )
    (net (code "94") (name "PA36") (class "Default")
      (node (ref "LCD1") (pin "11") (pinfunction "C~{D}_11") (pintype "bidirectional"))
      (node (ref "U61") (pin "5") (pinfunction "PA3_5") (pintype "bidirectional"))
    )
    (net (code "95") (name "PA45") (class "Default")
      (node (ref "IC52") (pin "5") (pinfunction "QF_5") (pintype "tri_state"))
      (node (ref "U51") (pin "6") (pinfunction "PA4_6") (pintype "bidirectional"))
    )
    (net (code "96") (name "PA46") (class "Default")
      (node (ref "LCD1") (pin "12") (pinfunction "~{HALT}_12") (pintype "bidirectional"))
      (node (ref "U61") (pin "6") (pinfunction "PA4_6") (pintype "bidirectional"))
    )
    (net (code "97") (name "PA55") (class "Default")
      (node (ref "IC52") (pin "4") (pinfunction "QE_4") (pintype "tri_state"))
      (node (ref "U51") (pin "7") (pinfunction "PA5_7") (pintype "bidirectional"))
    )
    (net (code "98") (name "PA56") (class "Default")
      (node (ref "LCD1") (pin "13") (pinfunction "~{RST}_13") (pintype "bidirectional"))
      (node (ref "U61") (pin "7") (pinfunction "PA5_7") (pintype "bidirectional"))
    )
    (net (code "99") (name "PA65") (class "Default")
      (node (ref "IC52") (pin "3") (pinfunction "QD_3") (pintype "tri_state"))
      (node (ref "U51") (pin "8") (pinfunction "PA6_8") (pintype "bidirectional"))
    )
    (net (code "100") (name "PA75") (class "Default")
      (node (ref "IC52") (pin "2") (pinfunction "QC_2") (pintype "tri_state"))
      (node (ref "U51") (pin "9") (pinfunction "PA7_9") (pintype "bidirectional"))
    )
    (net (code "101") (name "PB06") (class "Default")
      (node (ref "LCD1") (pin "14") (pinfunction "DB0_14") (pintype "input"))
      (node (ref "U61") (pin "10") (pinfunction "PB0_10") (pintype "bidirectional"))
    )
    (net (code "102") (name "PB16") (class "Default")
      (node (ref "LCD1") (pin "15") (pinfunction "DB1_15") (pintype "input"))
      (node (ref "U61") (pin "11") (pinfunction "PB1_11") (pintype "bidirectional"))
    )
    (net (code "103") (name "PB26") (class "Default")
      (node (ref "LCD1") (pin "16") (pinfunction "DB2_16") (pintype "input"))
      (node (ref "U61") (pin "12") (pinfunction "PB2_12") (pintype "bidirectional"))
    )
    (net (code "104") (name "PB36") (class "Default")
      (node (ref "LCD1") (pin "17") (pinfunction "DB3_17") (pintype "input"))
      (node (ref "U61") (pin "13") (pinfunction "PB3_13") (pintype "bidirectional"))
    )
    (net (code "105") (name "PB46") (class "Default")
      (node (ref "LCD1") (pin "18") (pinfunction "DB4_18") (pintype "input"))
      (node (ref "U61") (pin "14") (pinfunction "PB4_14") (pintype "bidirectional"))
    )
    (net (code "106") (name "PB56") (class "Default")
      (node (ref "LCD1") (pin "19") (pinfunction "DB5_19") (pintype "input"))
      (node (ref "U61") (pin "15") (pinfunction "PB5_15") (pintype "bidirectional"))
    )
    (net (code "107") (name "PB66") (class "Default")
      (node (ref "LCD1") (pin "20") (pinfunction "DB6_20") (pintype "input"))
      (node (ref "U61") (pin "16") (pinfunction "PB6_16") (pintype "bidirectional"))
    )
    (net (code "108") (name "PB76") (class "Default")
      (node (ref "LCD1") (pin "21") (pinfunction "DB7_21") (pintype "input"))
      (node (ref "U61") (pin "17") (pinfunction "PB7_17") (pintype "bidirectional"))
    )
    (net (code "109") (name "PHI0") (class "Default")
      (node (ref "IC25") (pin "10") (pinfunction "I1_10") (pintype "input"))
      (node (ref "IC25") (pin "4") (pinfunction "I0_4") (pintype "input"))
      (node (ref "JP1") (pin "3") (pinfunction "3_3") (pintype "passive"))
      (node (ref "QG1") (pin "8") (pinfunction "OUT_8") (pintype "output"))
      (node (ref "U11") (pin "37") (pinfunction "PHI2_37") (pintype "bidirectional"))
      (node (ref "U43") (pin "27") (pinfunction "PHI2_27") (pintype "bidirectional"))
      (node (ref "U51") (pin "25") (pinfunction "PHI2_25") (pintype "bidirectional"))
      (node (ref "U61") (pin "25") (pinfunction "PHI2_25") (pintype "bidirectional"))
    )
    (net (code "110") (name "PHI2OUT") (class "Default")
      (node (ref "U11") (pin "39") (pinfunction "PHI2OUT_39") (pintype "bidirectional"))
    )
    (net (code "111") (name "RDY") (class "Default")
      (node (ref "R14") (pin "2") (pinfunction "2_2") (pintype "passive"))
      (node (ref "U11") (pin "2") (pinfunction "RDY_2") (pintype "bidirectional"))
    )
    (net (code "112") (name "RXD") (class "Default")
      (node (ref "IC41") (pin "12") (pinfunction "R1OUT_12") (pintype "output"))
      (node (ref "U43") (pin "12") (pinfunction "RXD_12") (pintype "bidirectional"))
    )
    (net (code "113") (name "R{slash}~{W}") (class "Default")
      (node (ref "IC25") (pin "12") (pinfunction "I0_12") (pintype "input"))
      (node (ref "IC25") (pin "13") (pinfunction "I1_13") (pintype "input"))
      (node (ref "IC25") (pin "9") (pinfunction "I0_9") (pintype "input"))
      (node (ref "U11") (pin "34") (pinfunction "R/~{W}_34") (pintype "bidirectional"))
      (node (ref "U43") (pin "28") (pinfunction "R/~{W}_28") (pintype "bidirectional"))
      (node (ref "U51") (pin "22") (pinfunction "R/~{W}_22") (pintype "bidirectional"))
      (node (ref "U61") (pin "22") (pinfunction "R/~{W}_22") (pintype "bidirectional"))
    )
    (net (code "114") (name "SCK") (class "Default")
      (node (ref "IC52") (pin "11") (pinfunction "SCK_11") (pintype "input"))
      (node (ref "IC53") (pin "11") (pinfunction "SCK_11") (pintype "input"))
      (node (ref "IC57") (pin "12") (pinfunction "O_12") (pintype "output"))
    )
    (net (code "115") (name "SYNC") (class "Default")
      (node (ref "U11") (pin "7") (pinfunction "SYNC_7") (pintype "input"))
    )
    (net (code "116") (name "TXD") (class "Default")
      (node (ref "IC41") (pin "11") (pinfunction "T1IN_11") (pintype "input"))
      (node (ref "U43") (pin "10") (pinfunction "TXD_10") (pintype "bidirectional"))
    )
    (net (code "117") (name "VCC") (class "Default")
      (node (ref "C13") (pin "2") (pinfunction "2_2") (pintype "passive"))
      (node (ref "C14") (pin "2") (pinfunction "2_2") (pintype "passive"))
      (node (ref "C15") (pin "2") (pinfunction "2_2") (pintype "passive"))
      (node (ref "C21") (pin "2") (pinfunction "2_2") (pintype "passive"))
      (node (ref "C22") (pin "2") (pinfunction "2_2") (pintype "passive"))
      (node (ref "C23") (pin "2") (pinfunction "2_2") (pintype "passive"))
      (node (ref "C24") (pin "2") (pinfunction "2_2") (pintype "passive"))
      (node (ref "C25") (pin "2") (pinfunction "2_2") (pintype "passive"))
      (node (ref "C31") (pin "2") (pinfunction "2_2") (pintype "passive"))
      (node (ref "C32") (pin "2") (pinfunction "2_2") (pintype "passive"))
      (node (ref "C33") (pin "2") (pinfunction "2_2") (pintype "passive"))
      (node (ref "C34") (pin "2") (pinfunction "2_2") (pintype "passive"))
      (node (ref "C46") (pin "2") (pinfunction "2_2") (pintype "passive"))
      (node (ref "C47") (pin "2") (pinfunction "2_2") (pintype "passive"))
      (node (ref "C48") (pin "2") (pinfunction "2_2") (pintype "passive"))
      (node (ref "C52") (pin "2") (pinfunction "2_2") (pintype "passive"))
      (node (ref "C53") (pin "2") (pinfunction "2_2") (pintype "passive"))
      (node (ref "C54") (pin "2") (pinfunction "2_2") (pintype "passive"))
      (node (ref "C55") (pin "2") (pinfunction "2_2") (pintype "passive"))
      (node (ref "C56") (pin "2") (pinfunction "2_2") (pintype "passive"))
      (node (ref "C57") (pin "2") (pinfunction "2_2") (pintype "passive"))
      (node (ref "C61") (pin "2") (pinfunction "2_2") (pintype "passive"))
      (node (ref "C63") (pin "2") (pinfunction "2_2") (pintype "passive"))
      (node (ref "IC12") (pin "4") (pinfunction "/RES_4") (pintype "input"))
      (node (ref "IC12") (pin "8") (pinfunction "VCC+_8") (pintype "power_in"))
      (node (ref "IC13") (pin "14") (pinfunction "VCC_14") (pintype "power_in"))
      (node (ref "IC21") (pin "28") (pinfunction "VCC_28") (pintype "power_in"))
      (node (ref "IC22") (pin "16") (pinfunction "VCC_16") (pintype "power_in"))
      (node (ref "IC23") (pin "14") (pinfunction "VCC_14") (pintype "power_in"))
      (node (ref "IC24") (pin "14") (pinfunction "VCC_14") (pintype "power_in"))
      (node (ref "IC25") (pin "14") (pinfunction "VCC_14") (pintype "power_in"))
      (node (ref "IC32") (pin "16") (pinfunction "VCC_16") (pintype "power_in"))
      (node (ref "IC33") (pin "10") (pinfunction "I1_10") (pintype "input"))
      (node (ref "IC33") (pin "14") (pinfunction "VCC_14") (pintype "power_in"))
      (node (ref "IC33") (pin "9") (pinfunction "I0_9") (pintype "input"))
      (node (ref "IC34") (pin "14") (pinfunction "VCC_14") (pintype "power_in"))
      (node (ref "IC41") (pin "16") (pinfunction "VCC_16") (pintype "power_in"))
      (node (ref "IC42") (pin "16") (pinfunction "VCC_16") (pintype "power_in"))
      (node (ref "IC52") (pin "10") (pinfunction "SCL_10") (pintype "input"))
      (node (ref "IC52") (pin "16") (pinfunction "VCC_16") (pintype "power_in"))
      (node (ref "IC53") (pin "10") (pinfunction "SCL_10") (pintype "input"))
      (node (ref "IC53") (pin "16") (pinfunction "VCC_16") (pintype "power_in"))
      (node (ref "IC54") (pin "16") (pinfunction "VCC_16") (pintype "power_in"))
      (node (ref "IC55") (pin "16") (pinfunction "VCC_16") (pintype "power_in"))
      (node (ref "IC56") (pin "16") (pinfunction "VCC_16") (pintype "power_in"))
      (node (ref "IC57") (pin "14") (pinfunction "VCC_14") (pintype "power_in"))
      (node (ref "IC63") (pin "16") (pinfunction "VCC_16") (pintype "power_in"))
      (node (ref "J1") (pin "3") (pinfunction "3_3") (pintype "passive"))
      (node (ref "JP1") (pin "1") (pinfunction "1_1") (pintype "passive"))
      (node (ref "LCD1") (pin "5") (pinfunction "VDD_5") (pintype "power_in"))
      (node (ref "LED1") (pin "A") (pinfunction "A_A") (pintype "passive"))
      (node (ref "QG1") (pin "14") (pinfunction "VCC_14") (pintype "power_in"))
      (node (ref "R11") (pin "2") (pinfunction "2_2") (pintype "passive"))
      (node (ref "R12") (pin "2") (pinfunction "2_2") (pintype "passive"))
      (node (ref "R13") (pin "2") (pinfunction "2_2") (pintype "passive"))
      (node (ref "R14") (pin "1") (pinfunction "1_1") (pintype "passive"))
      (node (ref "R15") (pin "1") (pinfunction "1_1") (pintype "passive"))
      (node (ref "R16") (pin "1") (pinfunction "1_1") (pintype "passive"))
      (node (ref "R17") (pin "2") (pinfunction "2_2") (pintype "passive"))
      (node (ref "R18") (pin "2") (pinfunction "2_2") (pintype "passive"))
      (node (ref "R31") (pin "2") (pinfunction "2_2") (pintype "passive"))
      (node (ref "R62") (pin "1") (pinfunction "1_1") (pintype "passive"))
      (node (ref "U11") (pin "8") (pinfunction "VCC_8") (pintype "power_in"))
      (node (ref "U43") (pin "15") (pinfunction "VCC_15") (pintype "bidirectional"))
      (node (ref "U51") (pin "20") (pinfunction "VCC_20") (pintype "bidirectional"))
      (node (ref "U61") (pin "20") (pinfunction "VCC_20") (pintype "bidirectional"))
      (node (ref "X2") (pin "5") (pinfunction "5_5") (pintype "passive"))
      (node (ref "ZX1-28C256") (pin "28") (pinfunction "28_28") (pintype "passive"))
    )
    (net (code "118") (name "WE") (class "Default")
      (node (ref "IC21") (pin "27") (pinfunction "~{WE}_27") (pintype "input"))
      (node (ref "IC25") (pin "6") (pinfunction "O_6") (pintype "output"))
    )
    (net (code "119") (name "YH5") (class "Default")
      (node (ref "IC54") (pin "10") (pinfunction "Y5_10") (pintype "output"))
      (node (ref "IC55") (pin "4") (pinfunction "G2A_4") (pintype "input"))
      (node (ref "IC63") (pin "4") (pinfunction "G2A_4") (pintype "input"))
    )
    (net (code "120") (name "YL5") (class "Default")
      (node (ref "IC55") (pin "5") (pinfunction "G2B_5") (pintype "input"))
      (node (ref "IC56") (pin "15") (pinfunction "Y0_15") (pintype "output"))
    )
    (net (code "121") (name "YL6") (class "Default")
      (node (ref "IC56") (pin "14") (pinfunction "Y1_14") (pintype "output"))
      (node (ref "IC63") (pin "5") (pinfunction "G2B_5") (pintype "input"))
    )
    (net (code "122") (name "unconnected-(IC12-CON-Pad5)") (class "Default")
      (node (ref "IC12") (pin "5") (pinfunction "CON_5") (pintype "input"))
    )
    (net (code "123") (name "unconnected-(IC13B-O-Pad4)") (class "Default")
      (node (ref "IC13") (pin "4") (pinfunction "O_4") (pintype "output"))
    )
    (net (code "124") (name "unconnected-(IC13C-O-Pad6)") (class "Default")
      (node (ref "IC13") (pin "6") (pinfunction "O_6") (pintype "output"))
    )
    (net (code "125") (name "unconnected-(IC13D-O-Pad8)") (class "Default")
      (node (ref "IC13") (pin "8") (pinfunction "O_8") (pintype "output"))
    )
    (net (code "126") (name "unconnected-(IC13E-O-Pad10)") (class "Default")
      (node (ref "IC13") (pin "10") (pinfunction "O_10") (pintype "output"))
    )
    (net (code "127") (name "unconnected-(IC13F-O-Pad12)") (class "Default")
      (node (ref "IC13") (pin "12") (pinfunction "O_12") (pintype "output"))
    )
    (net (code "128") (name "unconnected-(IC24D-O-Pad11)") (class "Default")
      (node (ref "IC24") (pin "11") (pinfunction "O_11") (pintype "output"))
    )
    (net (code "129") (name "unconnected-(IC32A-Y4-Pad11)") (class "Default")
      (node (ref "IC32") (pin "11") (pinfunction "Y4_11") (pintype "output"))
    )
    (net (code "130") (name "unconnected-(IC32A-Y5-Pad10)") (class "Default")
      (node (ref "IC32") (pin "10") (pinfunction "Y5_10") (pintype "output"))
    )
    (net (code "131") (name "unconnected-(IC34D-O-Pad11)") (class "Default")
      (node (ref "IC34") (pin "11") (pinfunction "O_11") (pintype "output"))
    )
    (net (code "132") (name "unconnected-(IC41A-R2IN-Pad8)") (class "Default")
      (node (ref "IC41") (pin "8") (pinfunction "R2IN_8") (pintype "input"))
    )
    (net (code "133") (name "unconnected-(IC41A-R2OUT-Pad9)") (class "Default")
      (node (ref "IC41") (pin "9") (pinfunction "R2OUT_9") (pintype "output"))
    )
    (net (code "134") (name "unconnected-(IC41A-T2IN-Pad10)") (class "Default")
      (node (ref "IC41") (pin "10") (pinfunction "T2IN_10") (pintype "input"))
    )
    (net (code "135") (name "unconnected-(IC41A-T2OUT-Pad7)") (class "Default")
      (node (ref "IC41") (pin "7") (pinfunction "T2OUT_7") (pintype "output"))
    )
    (net (code "136") (name "unconnected-(IC42A-Y0-Pad15)") (class "Default")
      (node (ref "IC42") (pin "15") (pinfunction "Y0_15") (pintype "output"))
    )
    (net (code "137") (name "unconnected-(IC42A-Y1-Pad14)") (class "Default")
      (node (ref "IC42") (pin "14") (pinfunction "Y1_14") (pintype "output"))
    )
    (net (code "138") (name "unconnected-(IC42A-Y2-Pad13)") (class "Default")
      (node (ref "IC42") (pin "13") (pinfunction "Y2_13") (pintype "output"))
    )
    (net (code "139") (name "unconnected-(IC42A-Y3-Pad12)") (class "Default")
      (node (ref "IC42") (pin "12") (pinfunction "Y3_12") (pintype "output"))
    )
    (net (code "140") (name "unconnected-(IC42A-Y5-Pad10)") (class "Default")
      (node (ref "IC42") (pin "10") (pinfunction "Y5_10") (pintype "output"))
    )
    (net (code "141") (name "unconnected-(IC42A-Y6-Pad9)") (class "Default")
      (node (ref "IC42") (pin "9") (pinfunction "Y6_9") (pintype "output"))
    )
    (net (code "142") (name "unconnected-(IC42A-Y7-Pad7)") (class "Default")
      (node (ref "IC42") (pin "7") (pinfunction "Y7_7") (pintype "output"))
    )
    (net (code "143") (name "unconnected-(IC52A-QA-Pad15)") (class "Default")
      (node (ref "IC52") (pin "15") (pinfunction "QA_15") (pintype "tri_state"))
    )
    (net (code "144") (name "unconnected-(IC52A-QB-Pad1)") (class "Default")
      (node (ref "IC52") (pin "1") (pinfunction "QB_1") (pintype "tri_state"))
    )
    (net (code "145") (name "unconnected-(IC53A-QC-Pad2)") (class "Default")
      (node (ref "IC53") (pin "2") (pinfunction "QC_2") (pintype "tri_state"))
    )
    (net (code "146") (name "unconnected-(IC53A-QD-Pad3)") (class "Default")
      (node (ref "IC53") (pin "3") (pinfunction "QD_3") (pintype "tri_state"))
    )
    (net (code "147") (name "unconnected-(IC53A-QE-Pad4)") (class "Default")
      (node (ref "IC53") (pin "4") (pinfunction "QE_4") (pintype "tri_state"))
    )
    (net (code "148") (name "unconnected-(IC53A-QF-Pad5)") (class "Default")
      (node (ref "IC53") (pin "5") (pinfunction "QF_5") (pintype "tri_state"))
    )
    (net (code "149") (name "unconnected-(IC53A-QG-Pad6)") (class "Default")
      (node (ref "IC53") (pin "6") (pinfunction "QG_6") (pintype "tri_state"))
    )
    (net (code "150") (name "unconnected-(IC53A-QH*-Pad9)") (class "Default")
      (node (ref "IC53") (pin "9") (pinfunction "QH*_9") (pintype "tri_state"))
    )
    (net (code "151") (name "unconnected-(IC53A-QH-Pad7)") (class "Default")
      (node (ref "IC53") (pin "7") (pinfunction "QH_7") (pintype "tri_state"))
    )
    (net (code "152") (name "unconnected-(IC54A-Y0-Pad15)") (class "Default")
      (node (ref "IC54") (pin "15") (pinfunction "Y0_15") (pintype "output"))
    )
    (net (code "153") (name "unconnected-(IC54A-Y1-Pad14)") (class "Default")
      (node (ref "IC54") (pin "14") (pinfunction "Y1_14") (pintype "output"))
    )
    (net (code "154") (name "unconnected-(IC54A-Y2-Pad13)") (class "Default")
      (node (ref "IC54") (pin "13") (pinfunction "Y2_13") (pintype "output"))
    )
    (net (code "155") (name "unconnected-(IC54A-Y3-Pad12)") (class "Default")
      (node (ref "IC54") (pin "12") (pinfunction "Y3_12") (pintype "output"))
    )
    (net (code "156") (name "unconnected-(IC54A-Y4-Pad11)") (class "Default")
      (node (ref "IC54") (pin "11") (pinfunction "Y4_11") (pintype "output"))
    )
    (net (code "157") (name "unconnected-(IC54A-Y6-Pad9)") (class "Default")
      (node (ref "IC54") (pin "9") (pinfunction "Y6_9") (pintype "output"))
    )
    (net (code "158") (name "unconnected-(IC54A-Y7-Pad7)") (class "Default")
      (node (ref "IC54") (pin "7") (pinfunction "Y7_7") (pintype "output"))
    )
    (net (code "159") (name "unconnected-(IC55A-Y1-Pad14)") (class "Default")
      (node (ref "IC55") (pin "14") (pinfunction "Y1_14") (pintype "output"))
    )
    (net (code "160") (name "unconnected-(IC55A-Y2-Pad13)") (class "Default")
      (node (ref "IC55") (pin "13") (pinfunction "Y2_13") (pintype "output"))
    )
    (net (code "161") (name "unconnected-(IC55A-Y3-Pad12)") (class "Default")
      (node (ref "IC55") (pin "12") (pinfunction "Y3_12") (pintype "output"))
    )
    (net (code "162") (name "unconnected-(IC55A-Y4-Pad11)") (class "Default")
      (node (ref "IC55") (pin "11") (pinfunction "Y4_11") (pintype "output"))
    )
    (net (code "163") (name "unconnected-(IC55A-Y5-Pad10)") (class "Default")
      (node (ref "IC55") (pin "10") (pinfunction "Y5_10") (pintype "output"))
    )
    (net (code "164") (name "unconnected-(IC55A-Y6-Pad9)") (class "Default")
      (node (ref "IC55") (pin "9") (pinfunction "Y6_9") (pintype "output"))
    )
    (net (code "165") (name "unconnected-(IC55A-Y7-Pad7)") (class "Default")
      (node (ref "IC55") (pin "7") (pinfunction "Y7_7") (pintype "output"))
    )
    (net (code "166") (name "unconnected-(IC56A-Y2-Pad13)") (class "Default")
      (node (ref "IC56") (pin "13") (pinfunction "Y2_13") (pintype "output"))
    )
    (net (code "167") (name "unconnected-(IC56A-Y3-Pad12)") (class "Default")
      (node (ref "IC56") (pin "12") (pinfunction "Y3_12") (pintype "output"))
    )
    (net (code "168") (name "unconnected-(IC56A-Y4-Pad11)") (class "Default")
      (node (ref "IC56") (pin "11") (pinfunction "Y4_11") (pintype "output"))
    )
    (net (code "169") (name "unconnected-(IC56A-Y5-Pad10)") (class "Default")
      (node (ref "IC56") (pin "10") (pinfunction "Y5_10") (pintype "output"))
    )
    (net (code "170") (name "unconnected-(IC56A-Y6-Pad9)") (class "Default")
      (node (ref "IC56") (pin "9") (pinfunction "Y6_9") (pintype "output"))
    )
    (net (code "171") (name "unconnected-(IC56A-Y7-Pad7)") (class "Default")
      (node (ref "IC56") (pin "7") (pinfunction "Y7_7") (pintype "output"))
    )
    (net (code "172") (name "unconnected-(IC57D-O-Pad2)") (class "Default")
      (node (ref "IC57") (pin "2") (pinfunction "O_2") (pintype "output"))
    )
    (net (code "173") (name "unconnected-(IC57E-O-Pad4)") (class "Default")
      (node (ref "IC57") (pin "4") (pinfunction "O_4") (pintype "output"))
    )
    (net (code "174") (name "unconnected-(IC57F-O-Pad6)") (class "Default")
      (node (ref "IC57") (pin "6") (pinfunction "O_6") (pintype "output"))
    )
    (net (code "175") (name "unconnected-(IC63A-Y1-Pad14)") (class "Default")
      (node (ref "IC63") (pin "14") (pinfunction "Y1_14") (pintype "output"))
    )
    (net (code "176") (name "unconnected-(IC63A-Y2-Pad13)") (class "Default")
      (node (ref "IC63") (pin "13") (pinfunction "Y2_13") (pintype "output"))
    )
    (net (code "177") (name "unconnected-(IC63A-Y3-Pad12)") (class "Default")
      (node (ref "IC63") (pin "12") (pinfunction "Y3_12") (pintype "output"))
    )
    (net (code "178") (name "unconnected-(IC63A-Y4-Pad11)") (class "Default")
      (node (ref "IC63") (pin "11") (pinfunction "Y4_11") (pintype "output"))
    )
    (net (code "179") (name "unconnected-(IC63A-Y5-Pad10)") (class "Default")
      (node (ref "IC63") (pin "10") (pinfunction "Y5_10") (pintype "output"))
    )
    (net (code "180") (name "unconnected-(IC63A-Y6-Pad9)") (class "Default")
      (node (ref "IC63") (pin "9") (pinfunction "Y6_9") (pintype "output"))
    )
    (net (code "181") (name "unconnected-(IC63A-Y7-Pad7)") (class "Default")
      (node (ref "IC63") (pin "7") (pinfunction "Y7_7") (pintype "output"))
    )
    (net (code "182") (name "unconnected-(J1-Pad2)") (class "Default")
      (node (ref "J1") (pin "2") (pinfunction "2_2") (pintype "passive"))
    )
    (net (code "183") (name "unconnected-(LCD1-NC-Pad22)") (class "Default")
      (node (ref "LCD1") (pin "22") (pinfunction "NC_22") (pintype "no_connect"))
    )
    (net (code "184") (name "unconnected-(LCD1-PIN1_NC-Pad1)") (class "Default")
      (node (ref "LCD1") (pin "1") (pinfunction "PIN1_NC_1") (pintype "no_connect"))
    )
    (net (code "185") (name "unconnected-(LCD1-PIN2_NC-Pad2)") (class "Default")
      (node (ref "LCD1") (pin "2") (pinfunction "PIN2_NC_2") (pintype "no_connect"))
    )
    (net (code "186") (name "unconnected-(LCD1-PIN25_NC-Pad25)") (class "Default")
      (node (ref "LCD1") (pin "25") (pinfunction "PIN25_NC_25") (pintype "no_connect"))
    )
    (net (code "187") (name "unconnected-(LCD1-PIN26_NC-Pad26)") (class "Default")
      (node (ref "LCD1") (pin "26") (pinfunction "PIN26_NC_26") (pintype "no_connect"))
    )
    (net (code "188") (name "unconnected-(QG1-TS-Pad1)") (class "Default")
      (node (ref "QG1") (pin "1") (pinfunction "TS_1") (pintype "passive"))
    )
    (net (code "189") (name "unconnected-(U11-NC-Pad35)") (class "Default")
      (node (ref "U11") (pin "35") (pinfunction "NC_35") (pintype "bidirectional"))
    )
    (net (code "190") (name "unconnected-(U11-PHI1OUT-Pad3)") (class "Default")
      (node (ref "U11") (pin "3") (pinfunction "PHI1OUT_3") (pintype "bidirectional"))
    )
    (net (code "191") (name "unconnected-(U11-~{ML}-Pad5)") (class "Default")
      (node (ref "U11") (pin "5") (pinfunction "~{ML}_5") (pintype "bidirectional"))
    )
    (net (code "192") (name "unconnected-(U43-RXC-Pad5)") (class "Default")
      (node (ref "U43") (pin "5") (pinfunction "RXC_5") (pintype "bidirectional"))
    )
    (net (code "193") (name "unconnected-(U43-~{DTR}-Pad11)") (class "Default")
      (node (ref "U43") (pin "11") (pinfunction "~{DTR}_11") (pintype "bidirectional"))
    )
    (net (code "194") (name "unconnected-(U43-~{RTS}-Pad8)") (class "Default")
      (node (ref "U43") (pin "8") (pinfunction "~{RTS}_8") (pintype "bidirectional"))
    )
    (net (code "195") (name "unconnected-(U51-CA2-Pad39)") (class "Default")
      (node (ref "U51") (pin "39") (pinfunction "CA2_39") (pintype "bidirectional"))
    )
    (net (code "196") (name "unconnected-(U51-CB1-Pad18)") (class "Default")
      (node (ref "U51") (pin "18") (pinfunction "CB1_18") (pintype "bidirectional"))
    )
    (net (code "197") (name "unconnected-(U51-CB2-Pad19)") (class "Default")
      (node (ref "U51") (pin "19") (pinfunction "CB2_19") (pintype "bidirectional"))
    )
    (net (code "198") (name "unconnected-(U51-PB0-Pad10)") (class "Default")
      (node (ref "U51") (pin "10") (pinfunction "PB0_10") (pintype "bidirectional"))
    )
    (net (code "199") (name "unconnected-(U51-PB1-Pad11)") (class "Default")
      (node (ref "U51") (pin "11") (pinfunction "PB1_11") (pintype "bidirectional"))
    )
    (net (code "200") (name "unconnected-(U51-PB2-Pad12)") (class "Default")
      (node (ref "U51") (pin "12") (pinfunction "PB2_12") (pintype "bidirectional"))
    )
    (net (code "201") (name "unconnected-(U51-PB3-Pad13)") (class "Default")
      (node (ref "U51") (pin "13") (pinfunction "PB3_13") (pintype "bidirectional"))
    )
    (net (code "202") (name "unconnected-(U51-PB4-Pad14)") (class "Default")
      (node (ref "U51") (pin "14") (pinfunction "PB4_14") (pintype "bidirectional"))
    )
    (net (code "203") (name "unconnected-(U51-PB5-Pad15)") (class "Default")
      (node (ref "U51") (pin "15") (pinfunction "PB5_15") (pintype "bidirectional"))
    )
    (net (code "204") (name "unconnected-(U51-PB6-Pad16)") (class "Default")
      (node (ref "U51") (pin "16") (pinfunction "PB6_16") (pintype "bidirectional"))
    )
    (net (code "205") (name "unconnected-(U51-PB7-Pad17)") (class "Default")
      (node (ref "U51") (pin "17") (pinfunction "PB7_17") (pintype "bidirectional"))
    )
    (net (code "206") (name "unconnected-(U61-CA1-Pad40)") (class "Default")
      (node (ref "U61") (pin "40") (pinfunction "CA1_40") (pintype "bidirectional"))
    )
    (net (code "207") (name "unconnected-(U61-CA2-Pad39)") (class "Default")
      (node (ref "U61") (pin "39") (pinfunction "CA2_39") (pintype "bidirectional"))
    )
    (net (code "208") (name "unconnected-(U61-CB1-Pad18)") (class "Default")
      (node (ref "U61") (pin "18") (pinfunction "CB1_18") (pintype "bidirectional"))
    )
    (net (code "209") (name "unconnected-(U61-CB2-Pad19)") (class "Default")
      (node (ref "U61") (pin "19") (pinfunction "CB2_19") (pintype "bidirectional"))
    )
    (net (code "210") (name "unconnected-(U61-PA6-Pad8)") (class "Default")
      (node (ref "U61") (pin "8") (pinfunction "PA6_8") (pintype "bidirectional"))
    )
    (net (code "211") (name "unconnected-(U61-PA7-Pad9)") (class "Default")
      (node (ref "U61") (pin "9") (pinfunction "PA7_9") (pintype "bidirectional"))
    )
    (net (code "212") (name "unconnected-(X1-Pad1)") (class "Default")
      (node (ref "X1") (pin "1") (pinfunction "1_1") (pintype "passive"))
    )
    (net (code "213") (name "unconnected-(X1-Pad4)") (class "Default")
      (node (ref "X1") (pin "4") (pinfunction "4_4") (pintype "passive"))
    )
    (net (code "214") (name "unconnected-(X1-Pad6)") (class "Default")
      (node (ref "X1") (pin "6") (pinfunction "6_6") (pintype "passive"))
    )
    (net (code "215") (name "unconnected-(X1-Pad7)") (class "Default")
      (node (ref "X1") (pin "7") (pinfunction "7_7") (pintype "passive"))
    )
    (net (code "216") (name "unconnected-(X1-Pad8)") (class "Default")
      (node (ref "X1") (pin "8") (pinfunction "8_8") (pintype "passive"))
    )
    (net (code "217") (name "unconnected-(X1-Pad9)") (class "Default")
      (node (ref "X1") (pin "9") (pinfunction "9_9") (pintype "passive"))
    )
    (net (code "218") (name "unconnected-(X2-Pad3)") (class "Default")
      (node (ref "X2") (pin "3") (pinfunction "3_3") (pintype "passive"))
    )
    (net (code "219") (name "~{CS1_SERIAL}") (class "Default")
      (node (ref "IC42") (pin "11") (pinfunction "Y4_11") (pintype "output"))
      (node (ref "U43") (pin "3") (pinfunction "~{CS1}_3") (pintype "bidirectional"))
    )
    (net (code "220") (name "~{CS2_KEYB}") (class "Default")
      (node (ref "IC55") (pin "15") (pinfunction "Y0_15") (pintype "output"))
      (node (ref "U51") (pin "23") (pinfunction "~{CS2}_23") (pintype "bidirectional"))
    )
    (net (code "221") (name "~{CS2_LCD}") (class "Default")
      (node (ref "IC63") (pin "15") (pinfunction "Y0_15") (pintype "output"))
      (node (ref "U61") (pin "23") (pinfunction "~{CS2}_23") (pintype "bidirectional"))
    )
    (net (code "222") (name "~{IRQ}") (class "Default")
      (node (ref "D41") (pin "A") (pinfunction "A_A") (pintype "passive"))
      (node (ref "D51") (pin "A") (pinfunction "A_A") (pintype "passive"))
      (node (ref "D61") (pin "A") (pinfunction "A_A") (pintype "passive"))
      (node (ref "JP11") (pin "1") (pinfunction "1_1") (pintype "passive"))
    )
    (net (code "223") (name "~{NMI}") (class "Default")
      (node (ref "JP12") (pin "1") (pinfunction "1_1") (pintype "passive"))
    )
    (net (code "224") (name "~{RESET}") (class "Default")
      (node (ref "IC13") (pin "2") (pinfunction "O_2") (pintype "output"))
      (node (ref "R13") (pin "1") (pinfunction "1_1") (pintype "passive"))
      (node (ref "U11") (pin "40") (pinfunction "~{RESET}_40") (pintype "bidirectional"))
      (node (ref "U43") (pin "4") (pinfunction "~{RES}_4") (pintype "bidirectional"))
      (node (ref "U51") (pin "34") (pinfunction "~{RESET}_34") (pintype "bidirectional"))
      (node (ref "U61") (pin "34") (pinfunction "~{RESET}_34") (pintype "bidirectional"))
    )
    (net (code "225") (name "~{SO}") (class "Default")
      (node (ref "R17") (pin "1") (pinfunction "1_1") (pintype "passive"))
      (node (ref "U11") (pin "38") (pinfunction "~{SO}_38") (pintype "bidirectional"))
    )
    (net (code "226") (name "~{VP}") (class "Default")
      (node (ref "JP13") (pin "2") (pinfunction "2_2") (pintype "passive"))
      (node (ref "U11") (pin "1") (pinfunction "~{VP}_1") (pintype "bidirectional"))
    )
  )
)
